# Replicape_B3.net
KiCad netlist of a schematic drawn in EAGLE
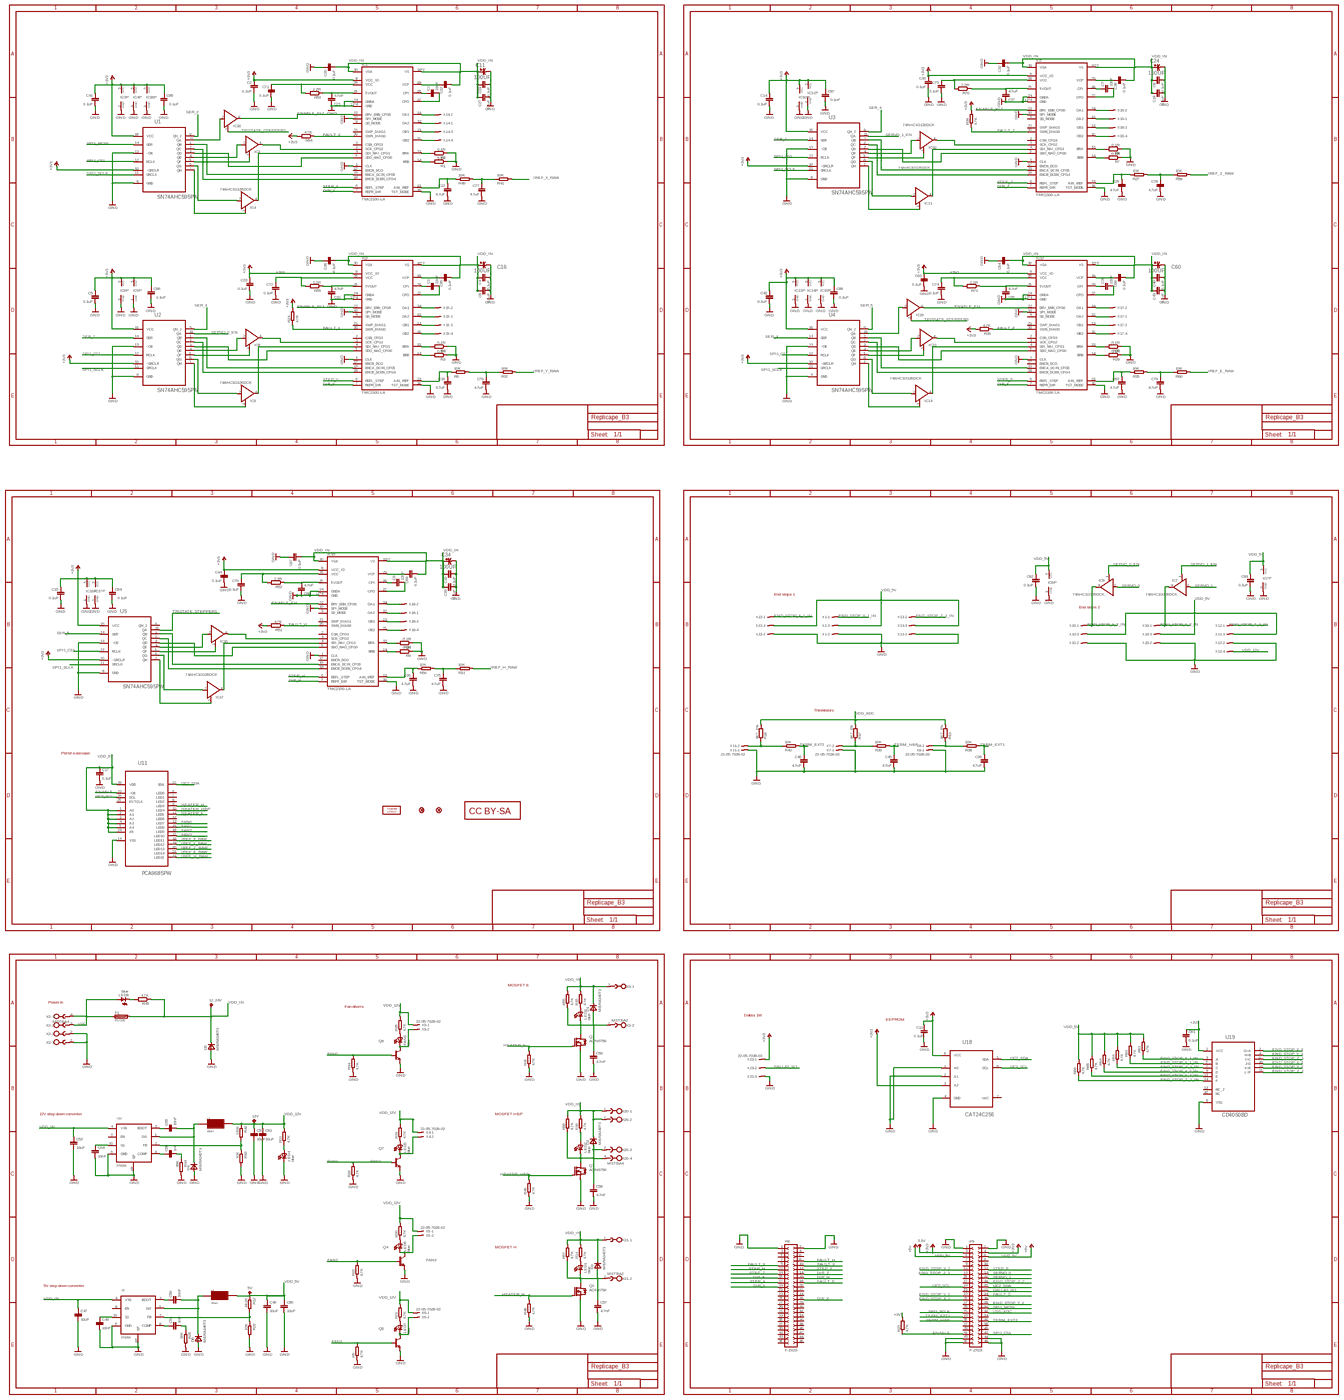
[diagram p0: schematic, sheet 1, overview]
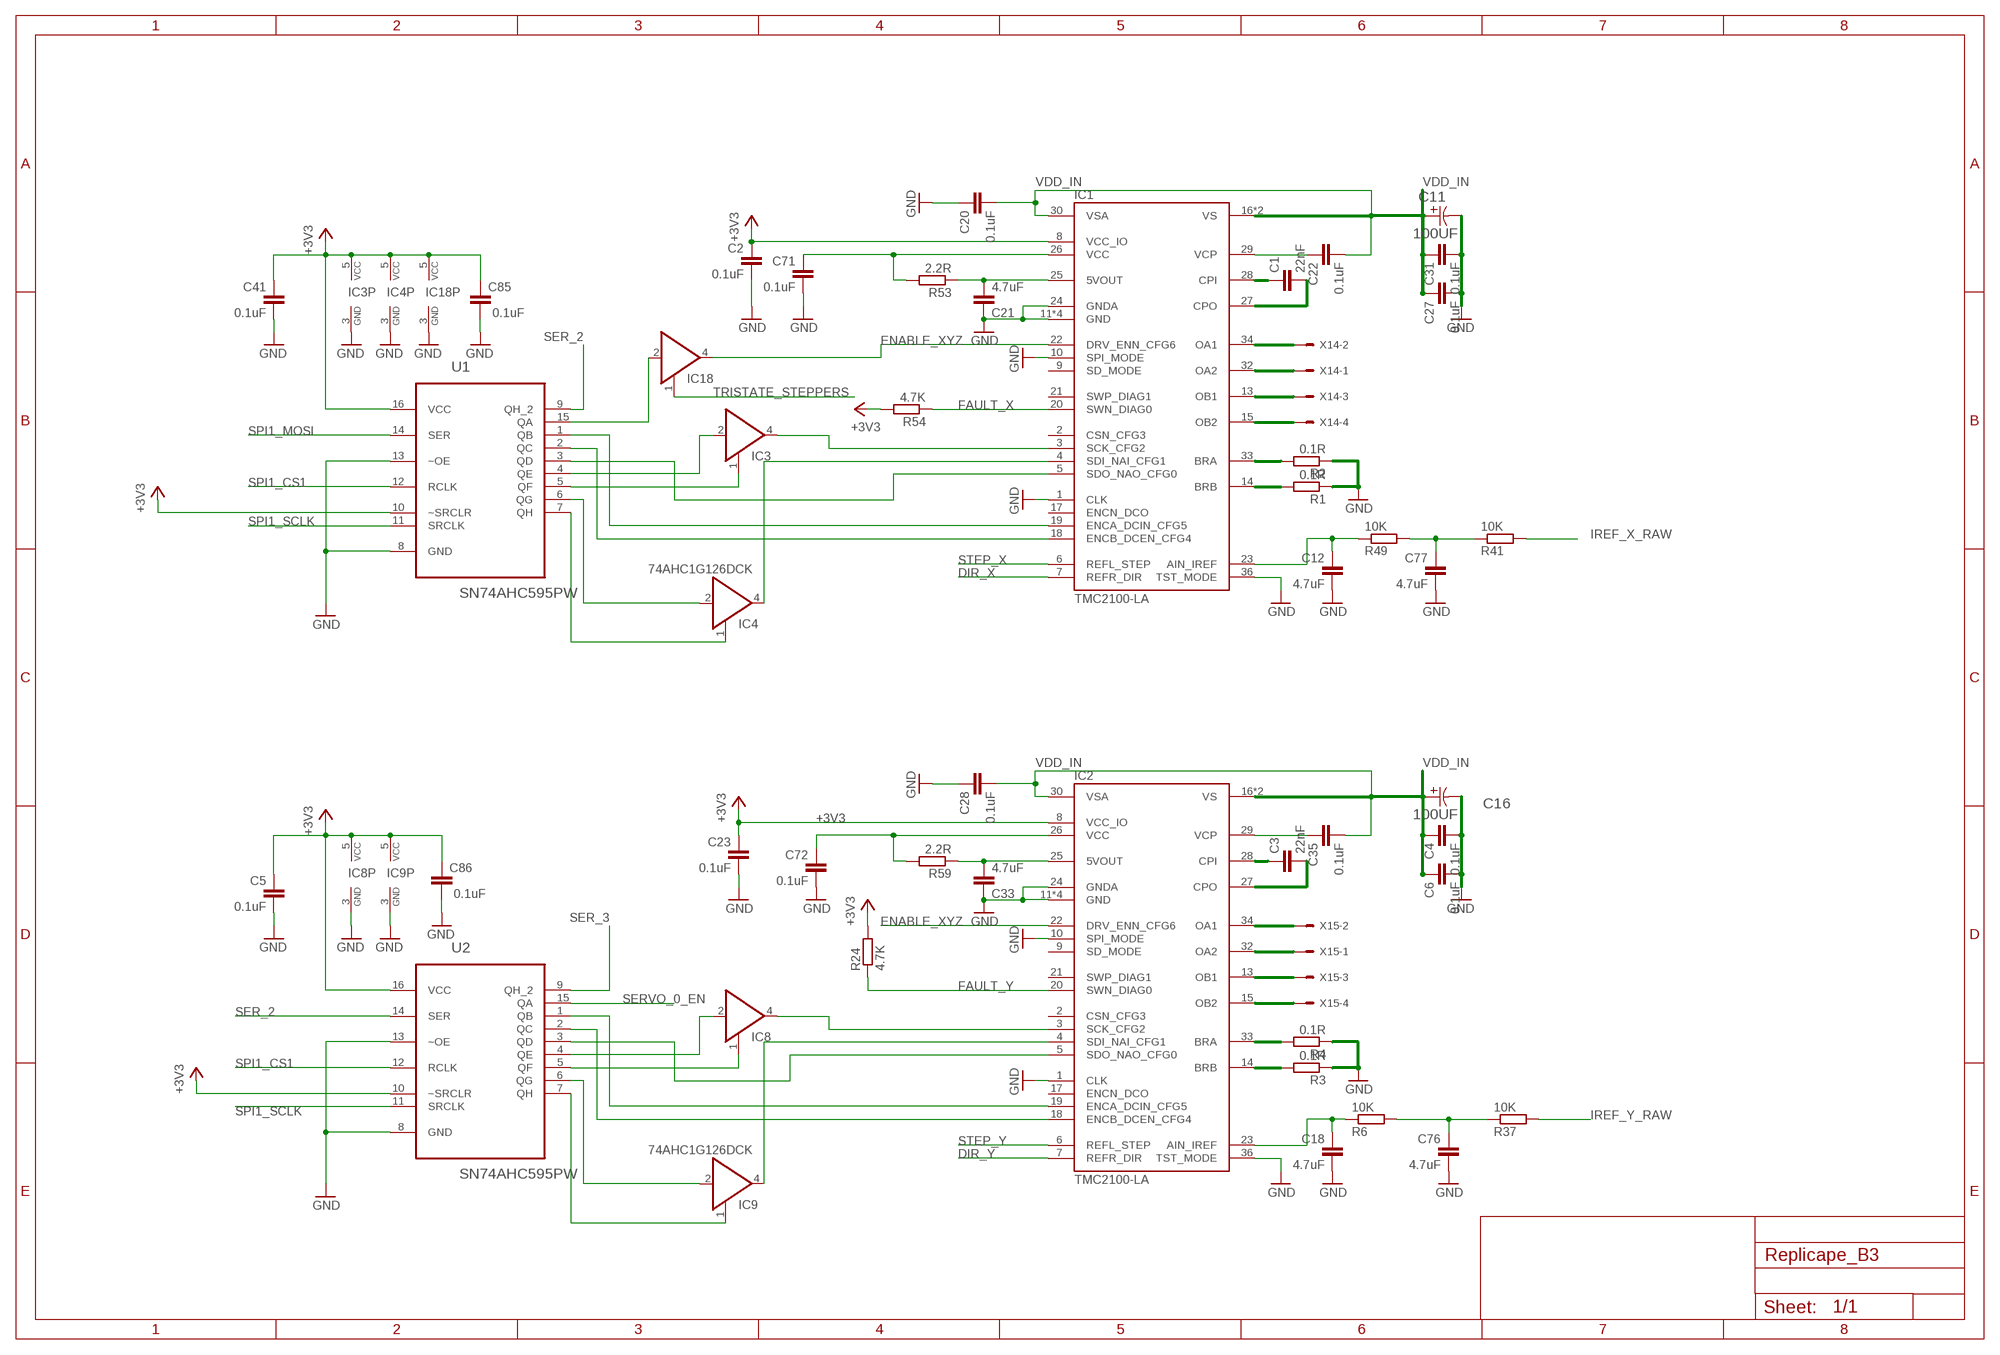
[diagram p1: schematic, sheet 1, part 1 of 4]
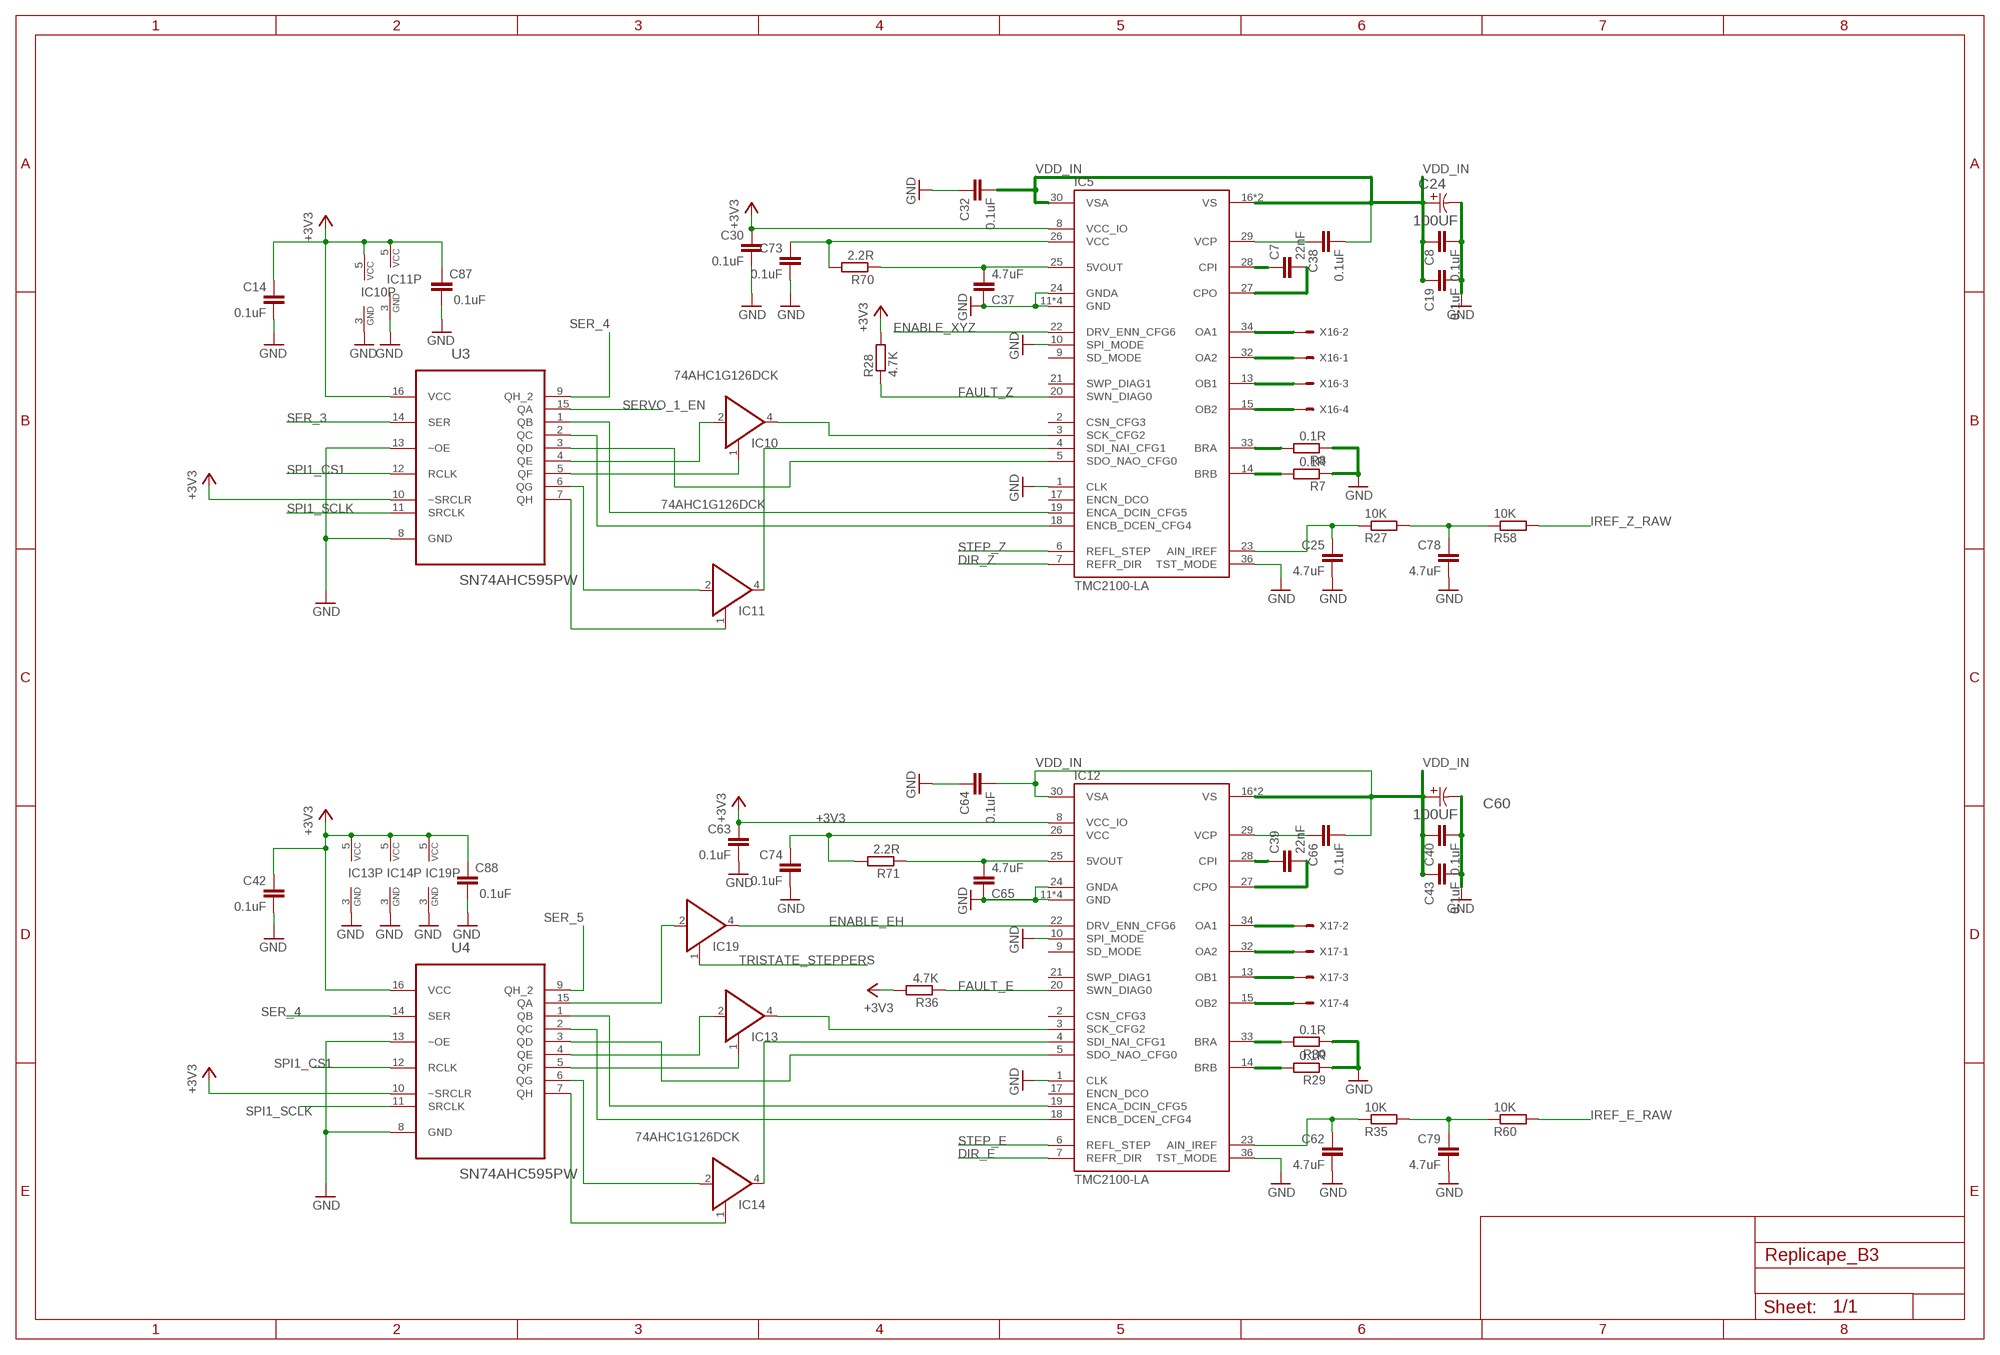
[diagram p2: schematic, sheet 1, part 2 of 4]
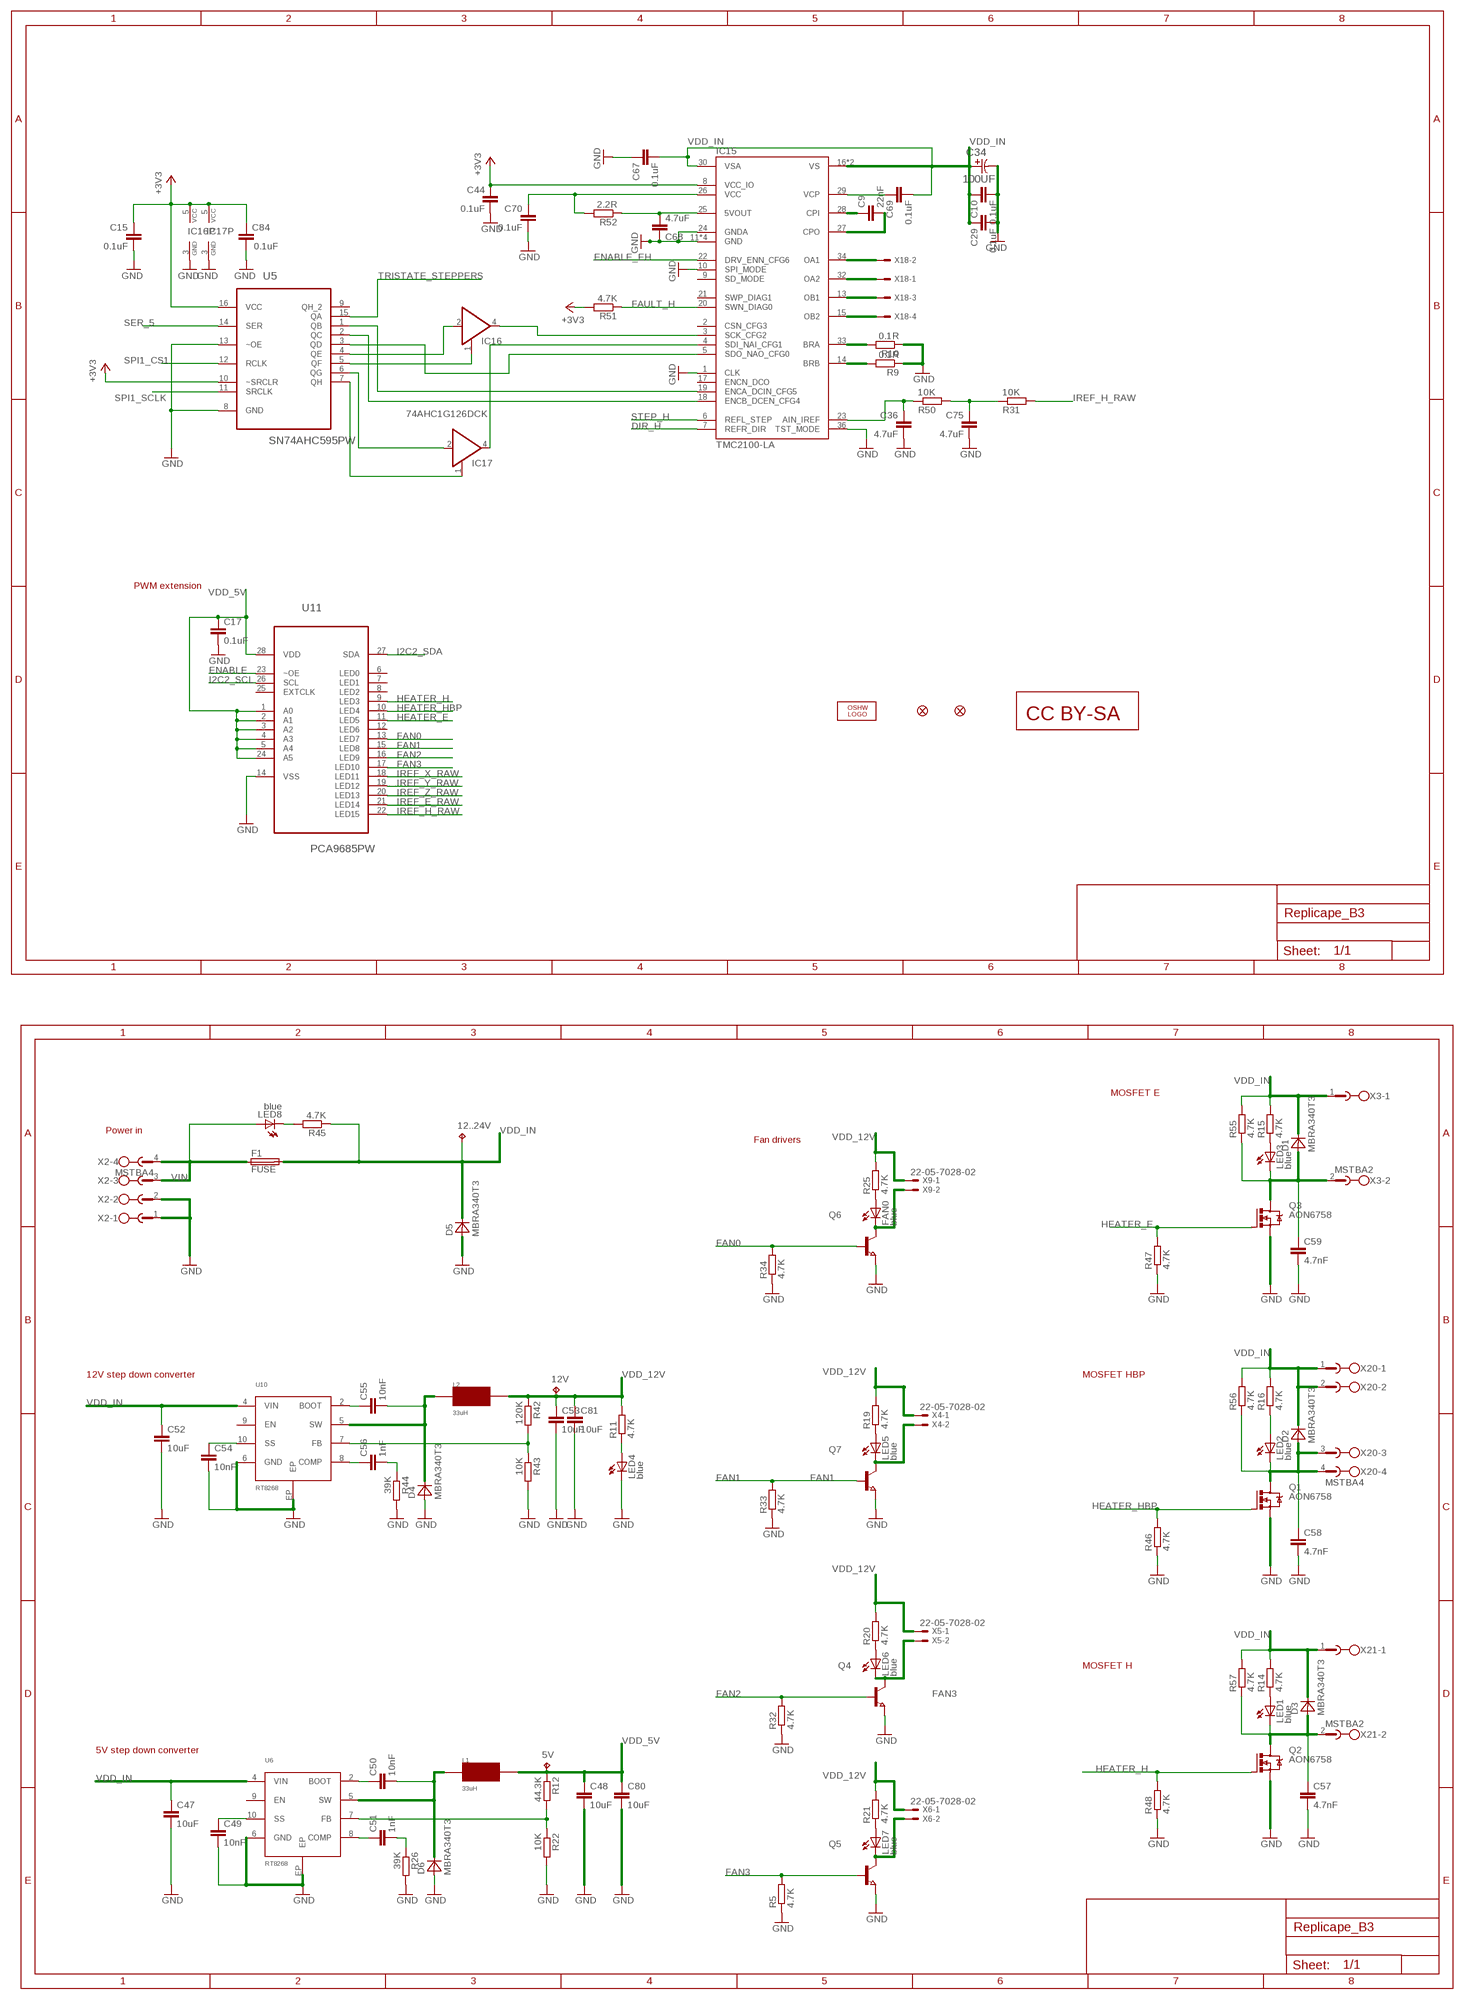
[diagram p3: schematic, sheet 1, part 3 of 4]
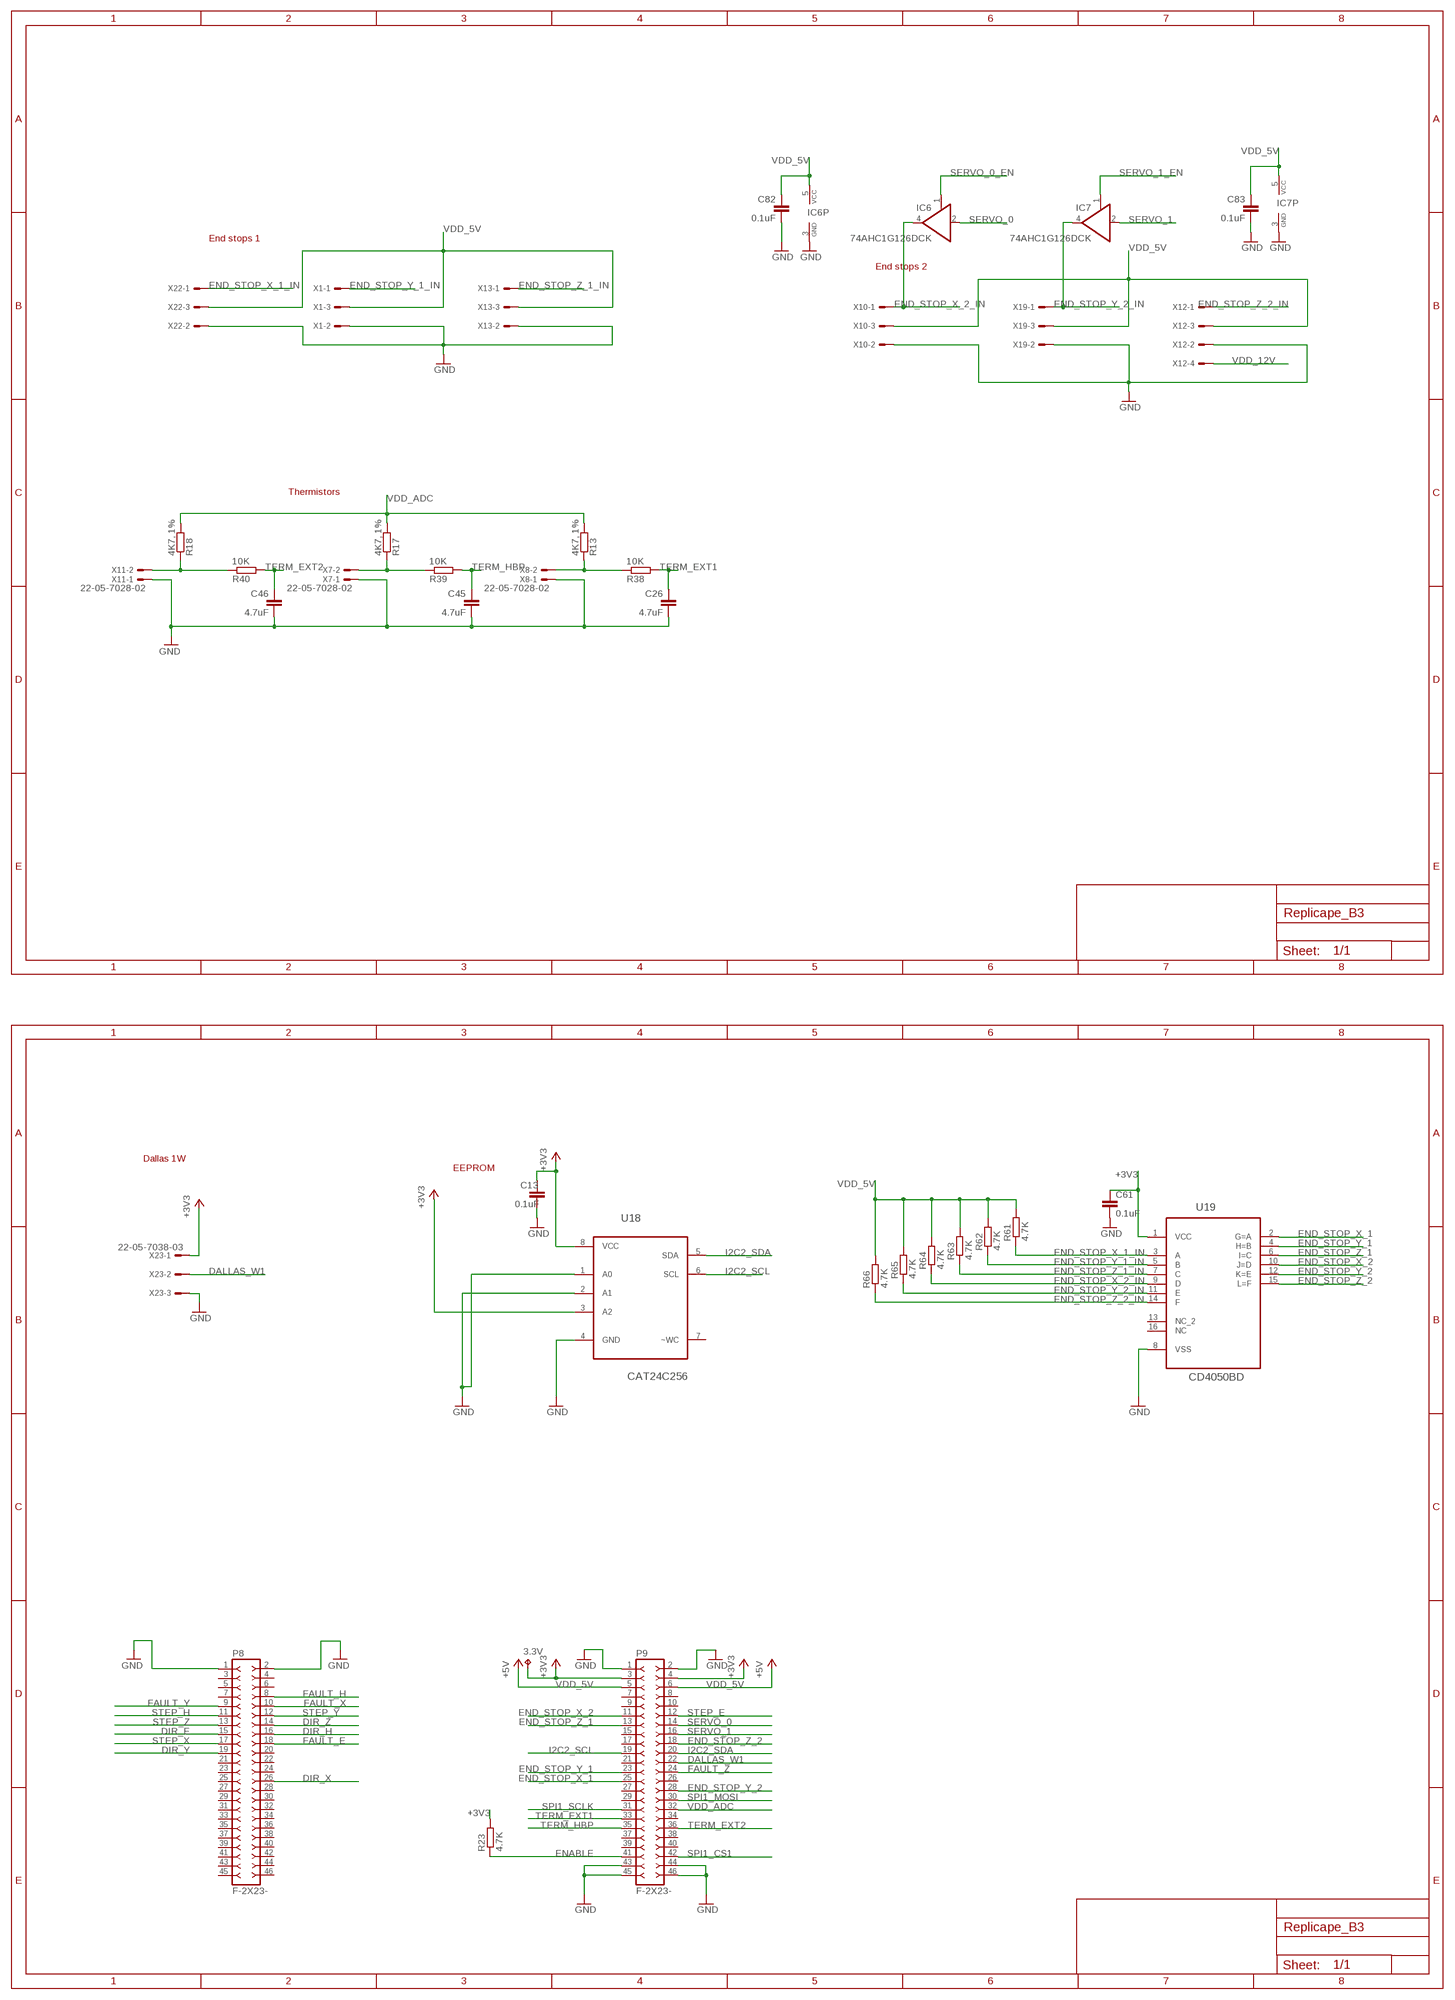
[diagram p4: schematic, sheet 1, part 4 of 4]

(export (version "E")
  (design (tool "Eeschema 10.0.6"))
  (components
    (comp (ref "3.3V")
      (value "TPB1,27")
      (footprint "eagle-import:B1,27")
      (libsource (lib "eagle-import") (part "TPB1,27"))
    )
    (comp (ref "5V")
      (value "TPB1,27")
      (footprint "eagle-import:B1,27")
      (libsource (lib "eagle-import") (part "TPB1,27"))
    )
    (comp (ref "12..24V")
      (value "TPB1,27")
      (footprint "eagle-import:B1,27")
      (libsource (lib "eagle-import") (part "TPB1,27"))
    )
    (comp (ref "12V")
      (value "TPB1,27")
      (footprint "eagle-import:B1,27")
      (libsource (lib "eagle-import") (part "TPB1,27"))
    )
    (comp (ref "C1")
      (value "22nF")
      (footprint "eagle-import:C0402")
      (libsource (lib "eagle-import") (part "C-EUC0402"))
    )
    (comp (ref "C2")
      (value "0.1uF")
      (footprint "eagle-import:C0402")
      (libsource (lib "eagle-import") (part "C-EUC0402"))
    )
    (comp (ref "C3")
      (value "22nF")
      (footprint "eagle-import:C0402")
      (libsource (lib "eagle-import") (part "C-EUC0402"))
    )
    (comp (ref "C4")
      (value "0.1uF")
      (footprint "eagle-import:C0402")
      (libsource (lib "eagle-import") (part "C-EUC0402"))
    )
    (comp (ref "C5")
      (value "0.1uF")
      (footprint "eagle-import:C0402")
      (libsource (lib "eagle-import") (part "C-EUC0402"))
    )
    (comp (ref "C6")
      (value "0.1uF")
      (footprint "eagle-import:C0402")
      (libsource (lib "eagle-import") (part "C-EUC0402"))
    )
    (comp (ref "C7")
      (value "22nF")
      (footprint "eagle-import:C0402")
      (libsource (lib "eagle-import") (part "C-EUC0402"))
    )
    (comp (ref "C8")
      (value "0.1uF")
      (footprint "eagle-import:C0402")
      (libsource (lib "eagle-import") (part "C-EUC0402"))
    )
    (comp (ref "C9")
      (value "22nF")
      (footprint "eagle-import:C0402")
      (libsource (lib "eagle-import") (part "C-EUC0402"))
    )
    (comp (ref "C10")
      (value "0.1uF")
      (footprint "eagle-import:C0402")
      (libsource (lib "eagle-import") (part "C-EUC0402"))
    )
    (comp (ref "C11")
      (value "100UF")
      (footprint "eagle-import:CAPAE660X800N")
      (fields (field (name "MPN") "EEE-FK1V101XP") (field (name "TOLERANCE") "±20 %"))
      (libsource (lib "eagle-import") (part "EEE--CASE-D8FK1V101XP"))
    )
    (comp (ref "C12")
      (value "4.7uF")
      (footprint "eagle-import:C0402")
      (libsource (lib "eagle-import") (part "C-EUC0402"))
    )
    (comp (ref "C13")
      (value "0.1uF")
      (footprint "eagle-import:C0402")
      (libsource (lib "eagle-import") (part "C-EUC0402"))
    )
    (comp (ref "C14")
      (value "0.1uF")
      (footprint "eagle-import:C0402")
      (libsource (lib "eagle-import") (part "C-EUC0402"))
    )
    (comp (ref "C15")
      (value "0.1uF")
      (footprint "eagle-import:C0402")
      (libsource (lib "eagle-import") (part "C-EUC0402"))
    )
    (comp (ref "C16")
      (value "100UF")
      (footprint "eagle-import:CAPAE660X800N")
      (fields (field (name "MPN") "EEE-FK1V101XP") (field (name "TOLERANCE") "±20 %"))
      (libsource (lib "eagle-import") (part "EEE--CASE-D8FK1V101XP"))
    )
    (comp (ref "C17")
      (value "0.1uF")
      (footprint "eagle-import:C0402")
      (libsource (lib "eagle-import") (part "C-EUC0402"))
    )
    (comp (ref "C18")
      (value "4.7uF")
      (footprint "eagle-import:C0402")
      (libsource (lib "eagle-import") (part "C-EUC0402"))
    )
    (comp (ref "C19")
      (value "0.1uF")
      (footprint "eagle-import:C0402")
      (libsource (lib "eagle-import") (part "C-EUC0402"))
    )
    (comp (ref "C20")
      (value "0.1uF")
      (footprint "eagle-import:C0402")
      (libsource (lib "eagle-import") (part "C-EUC0402"))
    )
    (comp (ref "C21")
      (value "4.7uF")
      (footprint "eagle-import:C0402")
      (libsource (lib "eagle-import") (part "C-EUC0402"))
    )
    (comp (ref "C22")
      (value "0.1uF")
      (footprint "eagle-import:C0402")
      (libsource (lib "eagle-import") (part "C-EUC0402"))
    )
    (comp (ref "C23")
      (value "0.1uF")
      (footprint "eagle-import:C0402")
      (libsource (lib "eagle-import") (part "C-EUC0402"))
    )
    (comp (ref "C24")
      (value "100UF")
      (footprint "eagle-import:CAPAE660X800N")
      (fields (field (name "MPN") "EEE-FK1V101XP") (field (name "TOLERANCE") "±20 %"))
      (libsource (lib "eagle-import") (part "EEE--CASE-D8FK1V101XP"))
    )
    (comp (ref "C25")
      (value "4.7uF")
      (footprint "eagle-import:C0402")
      (libsource (lib "eagle-import") (part "C-EUC0402"))
    )
    (comp (ref "C26")
      (value "4.7uF")
      (footprint "eagle-import:C0402")
      (libsource (lib "eagle-import") (part "C-EUC0402"))
    )
    (comp (ref "C27")
      (value "0.1uF")
      (footprint "eagle-import:C0402")
      (libsource (lib "eagle-import") (part "C-EUC0402"))
    )
    (comp (ref "C28")
      (value "0.1uF")
      (footprint "eagle-import:C0402")
      (libsource (lib "eagle-import") (part "C-EUC0402"))
    )
    (comp (ref "C29")
      (value "0.1uF")
      (footprint "eagle-import:C0402")
      (libsource (lib "eagle-import") (part "C-EUC0402"))
    )
    (comp (ref "C30")
      (value "0.1uF")
      (footprint "eagle-import:C0402")
      (libsource (lib "eagle-import") (part "C-EUC0402"))
    )
    (comp (ref "C31")
      (value "0.1uF")
      (footprint "eagle-import:C0402")
      (libsource (lib "eagle-import") (part "C-EUC0402"))
    )
    (comp (ref "C32")
      (value "0.1uF")
      (footprint "eagle-import:C0402")
      (libsource (lib "eagle-import") (part "C-EUC0402"))
    )
    (comp (ref "C33")
      (value "4.7uF")
      (footprint "eagle-import:C0402")
      (libsource (lib "eagle-import") (part "C-EUC0402"))
    )
    (comp (ref "C34")
      (value "100UF")
      (footprint "eagle-import:CAPAE660X800N")
      (fields (field (name "MPN") "EEE-FK1V101XP") (field (name "TOLERANCE") "±20 %"))
      (libsource (lib "eagle-import") (part "EEE--CASE-D8FK1V101XP"))
    )
    (comp (ref "C35")
      (value "0.1uF")
      (footprint "eagle-import:C0402")
      (libsource (lib "eagle-import") (part "C-EUC0402"))
    )
    (comp (ref "C36")
      (value "4.7uF")
      (footprint "eagle-import:C0402")
      (libsource (lib "eagle-import") (part "C-EUC0402"))
    )
    (comp (ref "C37")
      (value "4.7uF")
      (footprint "eagle-import:C0402")
      (libsource (lib "eagle-import") (part "C-EUC0402"))
    )
    (comp (ref "C38")
      (value "0.1uF")
      (footprint "eagle-import:C0402")
      (libsource (lib "eagle-import") (part "C-EUC0402"))
    )
    (comp (ref "C39")
      (value "22nF")
      (footprint "eagle-import:C0402")
      (libsource (lib "eagle-import") (part "C-EUC0402"))
    )
    (comp (ref "C40")
      (value "0.1uF")
      (footprint "eagle-import:C0402")
      (libsource (lib "eagle-import") (part "C-EUC0402"))
    )
    (comp (ref "C41")
      (value "0.1uF")
      (footprint "eagle-import:C0402")
      (libsource (lib "eagle-import") (part "C-EUC0402"))
    )
    (comp (ref "C42")
      (value "0.1uF")
      (footprint "eagle-import:C0402")
      (libsource (lib "eagle-import") (part "C-EUC0402"))
    )
    (comp (ref "C43")
      (value "0.1uF")
      (footprint "eagle-import:C0402")
      (libsource (lib "eagle-import") (part "C-EUC0402"))
    )
    (comp (ref "C44")
      (value "0.1uF")
      (footprint "eagle-import:C0402")
      (libsource (lib "eagle-import") (part "C-EUC0402"))
    )
    (comp (ref "C45")
      (value "4.7uF")
      (footprint "eagle-import:C0402")
      (libsource (lib "eagle-import") (part "C-EUC0402"))
    )
    (comp (ref "C46")
      (value "4.7uF")
      (footprint "eagle-import:C0402")
      (libsource (lib "eagle-import") (part "C-EUC0402"))
    )
    (comp (ref "C47")
      (value "10uF")
      (footprint "eagle-import:C1206")
      (libsource (lib "eagle-import") (part "C-EUC1206"))
    )
    (comp (ref "C48")
      (value "10uF")
      (footprint "eagle-import:C1206")
      (libsource (lib "eagle-import") (part "C-EUC1206"))
    )
    (comp (ref "C49")
      (value "10nF")
      (footprint "eagle-import:C0402")
      (libsource (lib "eagle-import") (part "C-EUC0402"))
    )
    (comp (ref "C50")
      (value "10nF")
      (footprint "eagle-import:C0402")
      (libsource (lib "eagle-import") (part "C-EUC0402"))
    )
    (comp (ref "C51")
      (value "1nF")
      (footprint "eagle-import:C0402")
      (libsource (lib "eagle-import") (part "C-EUC0402"))
    )
    (comp (ref "C52")
      (value "10uF")
      (footprint "eagle-import:C1206")
      (libsource (lib "eagle-import") (part "C-EUC1206"))
    )
    (comp (ref "C53")
      (value "10uF")
      (footprint "eagle-import:C1206")
      (libsource (lib "eagle-import") (part "C-EUC1206"))
    )
    (comp (ref "C54")
      (value "10nF")
      (footprint "eagle-import:C0402")
      (libsource (lib "eagle-import") (part "C-EUC0402"))
    )
    (comp (ref "C55")
      (value "10nF")
      (footprint "eagle-import:C0402")
      (libsource (lib "eagle-import") (part "C-EUC0402"))
    )
    (comp (ref "C56")
      (value "1nF")
      (footprint "eagle-import:C0402")
      (libsource (lib "eagle-import") (part "C-EUC0402"))
    )
    (comp (ref "C57")
      (value "4.7nF")
      (footprint "eagle-import:C0402")
      (libsource (lib "eagle-import") (part "C-EUC0402"))
    )
    (comp (ref "C58")
      (value "4.7nF")
      (footprint "eagle-import:C0402")
      (libsource (lib "eagle-import") (part "C-EUC0402"))
    )
    (comp (ref "C59")
      (value "4.7nF")
      (footprint "eagle-import:C0402")
      (libsource (lib "eagle-import") (part "C-EUC0402"))
    )
    (comp (ref "C60")
      (value "100UF")
      (footprint "eagle-import:CAPAE660X800N")
      (fields (field (name "MPN") "EEE-FK1V101XP") (field (name "TOLERANCE") "±20 %"))
      (libsource (lib "eagle-import") (part "EEE--CASE-D8FK1V101XP"))
    )
    (comp (ref "C61")
      (value "0.1uF")
      (footprint "eagle-import:C0402")
      (libsource (lib "eagle-import") (part "C-EUC0402"))
    )
    (comp (ref "C62")
      (value "4.7uF")
      (footprint "eagle-import:C0402")
      (libsource (lib "eagle-import") (part "C-EUC0402"))
    )
    (comp (ref "C63")
      (value "0.1uF")
      (footprint "eagle-import:C0402")
      (libsource (lib "eagle-import") (part "C-EUC0402"))
    )
    (comp (ref "C64")
      (value "0.1uF")
      (footprint "eagle-import:C0402")
      (libsource (lib "eagle-import") (part "C-EUC0402"))
    )
    (comp (ref "C65")
      (value "4.7uF")
      (footprint "eagle-import:C0402")
      (libsource (lib "eagle-import") (part "C-EUC0402"))
    )
    (comp (ref "C66")
      (value "0.1uF")
      (footprint "eagle-import:C0402")
      (libsource (lib "eagle-import") (part "C-EUC0402"))
    )
    (comp (ref "C67")
      (value "0.1uF")
      (footprint "eagle-import:C0402")
      (libsource (lib "eagle-import") (part "C-EUC0402"))
    )
    (comp (ref "C68")
      (value "4.7uF")
      (footprint "eagle-import:C0402")
      (libsource (lib "eagle-import") (part "C-EUC0402"))
    )
    (comp (ref "C69")
      (value "0.1uF")
      (footprint "eagle-import:C0402")
      (libsource (lib "eagle-import") (part "C-EUC0402"))
    )
    (comp (ref "C70")
      (value "0.1uF")
      (footprint "eagle-import:C0402")
      (libsource (lib "eagle-import") (part "C-EUC0402"))
    )
    (comp (ref "C71")
      (value "0.1uF")
      (footprint "eagle-import:C0402")
      (libsource (lib "eagle-import") (part "C-EUC0402"))
    )
    (comp (ref "C72")
      (value "0.1uF")
      (footprint "eagle-import:C0402")
      (libsource (lib "eagle-import") (part "C-EUC0402"))
    )
    (comp (ref "C73")
      (value "0.1uF")
      (footprint "eagle-import:C0402")
      (libsource (lib "eagle-import") (part "C-EUC0402"))
    )
    (comp (ref "C74")
      (value "0.1uF")
      (footprint "eagle-import:C0402")
      (libsource (lib "eagle-import") (part "C-EUC0402"))
    )
    (comp (ref "C75")
      (value "4.7uF")
      (footprint "eagle-import:C0402")
      (libsource (lib "eagle-import") (part "C-EUC0402"))
    )
    (comp (ref "C76")
      (value "4.7uF")
      (footprint "eagle-import:C0402")
      (libsource (lib "eagle-import") (part "C-EUC0402"))
    )
    (comp (ref "C77")
      (value "4.7uF")
      (footprint "eagle-import:C0402")
      (libsource (lib "eagle-import") (part "C-EUC0402"))
    )
    (comp (ref "C78")
      (value "4.7uF")
      (footprint "eagle-import:C0402")
      (libsource (lib "eagle-import") (part "C-EUC0402"))
    )
    (comp (ref "C79")
      (value "4.7uF")
      (footprint "eagle-import:C0402")
      (libsource (lib "eagle-import") (part "C-EUC0402"))
    )
    (comp (ref "C80")
      (value "10uF")
      (footprint "eagle-import:C1206")
      (libsource (lib "eagle-import") (part "C-EUC1206"))
    )
    (comp (ref "C81")
      (value "10uF")
      (footprint "eagle-import:C1206")
      (libsource (lib "eagle-import") (part "C-EUC1206"))
    )
    (comp (ref "C82")
      (value "0.1uF")
      (footprint "eagle-import:C0402")
      (libsource (lib "eagle-import") (part "C-EUC0402"))
    )
    (comp (ref "C83")
      (value "0.1uF")
      (footprint "eagle-import:C0402")
      (libsource (lib "eagle-import") (part "C-EUC0402"))
    )
    (comp (ref "C84")
      (value "0.1uF")
      (footprint "eagle-import:C0402")
      (libsource (lib "eagle-import") (part "C-EUC0402"))
    )
    (comp (ref "C85")
      (value "0.1uF")
      (footprint "eagle-import:C0402")
      (libsource (lib "eagle-import") (part "C-EUC0402"))
    )
    (comp (ref "C86")
      (value "0.1uF")
      (footprint "eagle-import:C0402")
      (libsource (lib "eagle-import") (part "C-EUC0402"))
    )
    (comp (ref "C87")
      (value "0.1uF")
      (footprint "eagle-import:C0402")
      (libsource (lib "eagle-import") (part "C-EUC0402"))
    )
    (comp (ref "C88")
      (value "0.1uF")
      (footprint "eagle-import:C0402")
      (libsource (lib "eagle-import") (part "C-EUC0402"))
    )
    (comp (ref "D1")
      (value "MBRA340T3")
      (footprint "eagle-import:SMA")
      (libsource (lib "eagle-import") (part "MBRA340T3"))
    )
    (comp (ref "D2")
      (value "MBRA340T3")
      (footprint "eagle-import:SMA")
      (libsource (lib "eagle-import") (part "MBRA340T3"))
    )
    (comp (ref "D3")
      (value "MBRA340T3")
      (footprint "eagle-import:SMA")
      (libsource (lib "eagle-import") (part "MBRA340T3"))
    )
    (comp (ref "D4")
      (value "MBRA340T3")
      (footprint "eagle-import:SMA")
      (libsource (lib "eagle-import") (part "MBRA340T3"))
    )
    (comp (ref "D5")
      (value "MBRA340T3")
      (footprint "eagle-import:SMA")
      (libsource (lib "eagle-import") (part "MBRA340T3"))
    )
    (comp (ref "D6")
      (value "MBRA340T3")
      (footprint "eagle-import:SMA")
      (libsource (lib "eagle-import") (part "MBRA340T3"))
    )
    (comp (ref "F1")
      (value "FUSE")
      (footprint "eagle-import:3557")
      (libsource (lib "eagle-import") (part "FUSE"))
    )
    (comp (ref "FAN0")
      (value "blue")
      (footprint "eagle-import:CHIP-LED0603")
      (libsource (lib "eagle-import") (part "LEDCHIP-LED0603"))
    )
    (comp (ref "IC1")
      (value "TMC2100-LA")
      (footprint "eagle-import:QFN36-PAD")
      (libsource (lib "eagle-import") (part "TMC2100-LA"))
    )
    (comp (ref "IC2")
      (value "TMC2100-LA")
      (footprint "eagle-import:QFN36-PAD")
      (libsource (lib "eagle-import") (part "TMC2100-LA"))
    )
    (comp (ref "IC3")
      (value "74AHC1G126DCK")
      (footprint "eagle-import:SC70-5")
      (libsource (lib "eagle-import") (part "741G126DCKAHC"))
    )
    (comp (ref "IC4")
      (value "74AHC1G126DCK")
      (footprint "eagle-import:SC70-5")
      (libsource (lib "eagle-import") (part "741G126DCKAHC"))
    )
    (comp (ref "IC5")
      (value "TMC2100-LA")
      (footprint "eagle-import:QFN36-PAD")
      (libsource (lib "eagle-import") (part "TMC2100-LA"))
    )
    (comp (ref "IC6")
      (value "74AHC1G126DCK")
      (footprint "eagle-import:SC70-5")
      (libsource (lib "eagle-import") (part "741G126DCKAHC"))
    )
    (comp (ref "IC7")
      (value "74AHC1G126DCK")
      (footprint "eagle-import:SC70-5")
      (libsource (lib "eagle-import") (part "741G126DCKAHC"))
    )
    (comp (ref "IC8")
      (value "74AHC1G126DCK")
      (footprint "eagle-import:SC70-5")
      (libsource (lib "eagle-import") (part "741G126DCKAHC"))
    )
    (comp (ref "IC9")
      (value "74AHC1G126DCK")
      (footprint "eagle-import:SC70-5")
      (libsource (lib "eagle-import") (part "741G126DCKAHC"))
    )
    (comp (ref "IC10")
      (value "74AHC1G126DCK")
      (footprint "eagle-import:SC70-5")
      (libsource (lib "eagle-import") (part "741G126DCKAHC"))
    )
    (comp (ref "IC11")
      (value "74AHC1G126DCK")
      (footprint "eagle-import:SC70-5")
      (libsource (lib "eagle-import") (part "741G126DCKAHC"))
    )
    (comp (ref "IC12")
      (value "TMC2100-LA")
      (footprint "eagle-import:QFN36-PAD")
      (libsource (lib "eagle-import") (part "TMC2100-LA"))
    )
    (comp (ref "IC13")
      (value "74AHC1G126DCK")
      (footprint "eagle-import:SC70-5")
      (libsource (lib "eagle-import") (part "741G126DCKAHC"))
    )
    (comp (ref "IC14")
      (value "74AHC1G126DCK")
      (footprint "eagle-import:SC70-5")
      (libsource (lib "eagle-import") (part "741G126DCKAHC"))
    )
    (comp (ref "IC15")
      (value "TMC2100-LA")
      (footprint "eagle-import:QFN36-PAD")
      (libsource (lib "eagle-import") (part "TMC2100-LA"))
    )
    (comp (ref "IC16")
      (value "74AHC1G126DCK")
      (footprint "eagle-import:SC70-5")
      (libsource (lib "eagle-import") (part "741G126DCKAHC"))
    )
    (comp (ref "IC17")
      (value "74AHC1G126DCK")
      (footprint "eagle-import:SC70-5")
      (libsource (lib "eagle-import") (part "741G126DCKAHC"))
    )
    (comp (ref "IC18")
      (value "74AHC1G126DCK")
      (footprint "eagle-import:SC70-5")
      (libsource (lib "eagle-import") (part "741G126DCKAHC"))
    )
    (comp (ref "IC19")
      (value "74AHC1G126DCK")
      (footprint "eagle-import:SC70-5")
      (libsource (lib "eagle-import") (part "741G126DCKAHC"))
    )
    (comp (ref "JP1")
      (value "FIDUCIAL1X2.5")
      (footprint "eagle-import:FIDUCIAL-1X2.5")
      (libsource (lib "eagle-import") (part "FIDUCIAL1X2.5"))
    )
    (comp (ref "JP2")
      (value "FIDUCIAL1X2.5")
      (footprint "eagle-import:FIDUCIAL-1X2.5")
      (libsource (lib "eagle-import") (part "FIDUCIAL1X2.5"))
    )
    (comp (ref "L1")
      (value "33uH")
      (footprint "eagle-import:NR8040T330")
      (libsource (lib "eagle-import") (part "RT8040T330"))
    )
    (comp (ref "L2")
      (value "33uH")
      (footprint "eagle-import:NR8040T330")
      (libsource (lib "eagle-import") (part "RT8040T330"))
    )
    (comp (ref "LED1")
      (value "blue")
      (footprint "eagle-import:CHIP-LED0603")
      (libsource (lib "eagle-import") (part "LEDCHIP-LED0603"))
    )
    (comp (ref "LED2")
      (value "blue")
      (footprint "eagle-import:CHIP-LED0603")
      (libsource (lib "eagle-import") (part "LEDCHIP-LED0603"))
    )
    (comp (ref "LED3")
      (value "blue")
      (footprint "eagle-import:CHIP-LED0603")
      (libsource (lib "eagle-import") (part "LEDCHIP-LED0603"))
    )
    (comp (ref "LED4")
      (value "blue")
      (footprint "eagle-import:CHIP-LED0603")
      (libsource (lib "eagle-import") (part "LEDCHIP-LED0603"))
    )
    (comp (ref "LED5")
      (value "blue")
      (footprint "eagle-import:CHIP-LED0603")
      (libsource (lib "eagle-import") (part "LEDCHIP-LED0603"))
    )
    (comp (ref "LED6")
      (value "blue")
      (footprint "eagle-import:CHIP-LED0603")
      (libsource (lib "eagle-import") (part "LEDCHIP-LED0603"))
    )
    (comp (ref "LED7")
      (value "blue")
      (footprint "eagle-import:CHIP-LED0603")
      (libsource (lib "eagle-import") (part "LEDCHIP-LED0603"))
    )
    (comp (ref "LED8")
      (value "blue")
      (footprint "eagle-import:CHIP-LED0603")
      (libsource (lib "eagle-import") (part "LEDCHIP-LED0603"))
    )
    (comp (ref "LOGO1")
      (value "OSHW_LOGO_FILLX0200-NT")
      (footprint "eagle-import:OSHW_FILLX200_NOTEXT")
      (libsource (lib "eagle-import") (part "OSHW_LOGO_FILLX0200-NT"))
    )
    (comp (ref "P8")
      (value "F-2X23-")
      (footprint "eagle-import:DIL-100-2X23")
      (libsource (lib "eagle-import") (part "F-2X23-"))
    )
    (comp (ref "P9")
      (value "F-2X23-")
      (footprint "eagle-import:DIL-100-2X23")
      (libsource (lib "eagle-import") (part "F-2X23-"))
    )
    (comp (ref "Q1")
      (value "AON6758")
      (footprint "eagle-import:8-DFN-EP-(5X6)")
      (libsource (lib "eagle-import") (part "AON6758"))
    )
    (comp (ref "Q2")
      (value "AON6758")
      (footprint "eagle-import:8-DFN-EP-(5X6)")
      (libsource (lib "eagle-import") (part "AON6758"))
    )
    (comp (ref "Q3")
      (value "AON6758")
      (footprint "eagle-import:8-DFN-EP-(5X6)")
      (libsource (lib "eagle-import") (part "AON6758"))
    )
    (comp (ref "Q4")
      (value "NPN-TRANSISTOR_SOT23")
      (footprint "eagle-import:SOT23")
      (libsource (lib "eagle-import") (part "NPN-TRANSISTOR_SOT23"))
    )
    (comp (ref "Q5")
      (value "NPN-TRANSISTOR_SOT23")
      (footprint "eagle-import:SOT23")
      (libsource (lib "eagle-import") (part "NPN-TRANSISTOR_SOT23"))
    )
    (comp (ref "Q6")
      (value "NPN-TRANSISTOR_SOT23")
      (footprint "eagle-import:SOT23")
      (libsource (lib "eagle-import") (part "NPN-TRANSISTOR_SOT23"))
    )
    (comp (ref "Q7")
      (value "NPN-TRANSISTOR_SOT23")
      (footprint "eagle-import:SOT23")
      (libsource (lib "eagle-import") (part "NPN-TRANSISTOR_SOT23"))
    )
    (comp (ref "R1")
      (value "0.1R")
      (footprint "eagle-import:R0805")
      (libsource (lib "eagle-import") (part "R-EU_R0805"))
    )
    (comp (ref "R2")
      (value "0.1R")
      (footprint "eagle-import:R0805")
      (libsource (lib "eagle-import") (part "R-EU_R0805"))
    )
    (comp (ref "R3")
      (value "0.1R")
      (footprint "eagle-import:R0805")
      (libsource (lib "eagle-import") (part "R-EU_R0805"))
    )
    (comp (ref "R4")
      (value "0.1R")
      (footprint "eagle-import:R0805")
      (libsource (lib "eagle-import") (part "R-EU_R0805"))
    )
    (comp (ref "R5")
      (value "4.7K")
      (footprint "eagle-import:R0402")
      (libsource (lib "eagle-import") (part "R-EU_R0402"))
    )
    (comp (ref "R6")
      (value "10K")
      (footprint "eagle-import:R0402")
      (libsource (lib "eagle-import") (part "R-EU_R0402"))
    )
    (comp (ref "R7")
      (value "0.1R")
      (footprint "eagle-import:R0805")
      (libsource (lib "eagle-import") (part "R-EU_R0805"))
    )
    (comp (ref "R8")
      (value "0.1R")
      (footprint "eagle-import:R0805")
      (libsource (lib "eagle-import") (part "R-EU_R0805"))
    )
    (comp (ref "R9")
      (value "0.1R")
      (footprint "eagle-import:R0805")
      (libsource (lib "eagle-import") (part "R-EU_R0805"))
    )
    (comp (ref "R10")
      (value "0.1R")
      (footprint "eagle-import:R0805")
      (libsource (lib "eagle-import") (part "R-EU_R0805"))
    )
    (comp (ref "R11")
      (value "4.7K")
      (footprint "eagle-import:R0402")
      (libsource (lib "eagle-import") (part "R-EU_R0402"))
    )
    (comp (ref "R12")
      (value "44.3K")
      (footprint "eagle-import:R0402")
      (libsource (lib "eagle-import") (part "R-EU_R0402"))
    )
    (comp (ref "R13")
      (value "4K7, 1%")
      (footprint "eagle-import:R0402")
      (libsource (lib "eagle-import") (part "R-EU_R0402"))
    )
    (comp (ref "R14")
      (value "4.7K")
      (footprint "eagle-import:R0402")
      (libsource (lib "eagle-import") (part "R-EU_R0402"))
    )
    (comp (ref "R15")
      (value "4.7K")
      (footprint "eagle-import:R0402")
      (libsource (lib "eagle-import") (part "R-EU_R0402"))
    )
    (comp (ref "R16")
      (value "4.7K")
      (footprint "eagle-import:R0402")
      (libsource (lib "eagle-import") (part "R-EU_R0402"))
    )
    (comp (ref "R17")
      (value "4K7, 1%")
      (footprint "eagle-import:R0402")
      (libsource (lib "eagle-import") (part "R-EU_R0402"))
    )
    (comp (ref "R18")
      (value "4K7, 1%")
      (footprint "eagle-import:R0402")
      (libsource (lib "eagle-import") (part "R-EU_R0402"))
    )
    (comp (ref "R19")
      (value "4.7K")
      (footprint "eagle-import:R0402")
      (libsource (lib "eagle-import") (part "R-EU_R0402"))
    )
    (comp (ref "R20")
      (value "4.7K")
      (footprint "eagle-import:R0402")
      (libsource (lib "eagle-import") (part "R-EU_R0402"))
    )
    (comp (ref "R21")
      (value "4.7K")
      (footprint "eagle-import:R0402")
      (libsource (lib "eagle-import") (part "R-EU_R0402"))
    )
    (comp (ref "R22")
      (value "10K")
      (footprint "eagle-import:R0402")
      (libsource (lib "eagle-import") (part "R-EU_R0402"))
    )
    (comp (ref "R23")
      (value "4.7K")
      (footprint "eagle-import:R0402")
      (libsource (lib "eagle-import") (part "R-EU_R0402"))
    )
    (comp (ref "R24")
      (value "4.7K")
      (footprint "eagle-import:R0402")
      (libsource (lib "eagle-import") (part "R-EU_R0402"))
    )
    (comp (ref "R25")
      (value "4.7K")
      (footprint "eagle-import:R0402")
      (libsource (lib "eagle-import") (part "R-EU_R0402"))
    )
    (comp (ref "R26")
      (value "39K")
      (footprint "eagle-import:R0402")
      (libsource (lib "eagle-import") (part "R-EU_R0402"))
    )
    (comp (ref "R27")
      (value "10K")
      (footprint "eagle-import:R0402")
      (libsource (lib "eagle-import") (part "R-EU_R0402"))
    )
    (comp (ref "R28")
      (value "4.7K")
      (footprint "eagle-import:R0402")
      (libsource (lib "eagle-import") (part "R-EU_R0402"))
    )
    (comp (ref "R29")
      (value "0.1R")
      (footprint "eagle-import:R0805")
      (libsource (lib "eagle-import") (part "R-EU_R0805"))
    )
    (comp (ref "R30")
      (value "0.1R")
      (footprint "eagle-import:R0805")
      (libsource (lib "eagle-import") (part "R-EU_R0805"))
    )
    (comp (ref "R31")
      (value "10K")
      (footprint "eagle-import:R0402")
      (libsource (lib "eagle-import") (part "R-EU_R0402"))
    )
    (comp (ref "R32")
      (value "4.7K")
      (footprint "eagle-import:R0402")
      (libsource (lib "eagle-import") (part "R-EU_R0402"))
    )
    (comp (ref "R33")
      (value "4.7K")
      (footprint "eagle-import:R0402")
      (libsource (lib "eagle-import") (part "R-EU_R0402"))
    )
    (comp (ref "R34")
      (value "4.7K")
      (footprint "eagle-import:R0402")
      (libsource (lib "eagle-import") (part "R-EU_R0402"))
    )
    (comp (ref "R35")
      (value "10K")
      (footprint "eagle-import:R0402")
      (libsource (lib "eagle-import") (part "R-EU_R0402"))
    )
    (comp (ref "R36")
      (value "4.7K")
      (footprint "eagle-import:R0402")
      (libsource (lib "eagle-import") (part "R-EU_R0402"))
    )
    (comp (ref "R37")
      (value "10K")
      (footprint "eagle-import:R0402")
      (libsource (lib "eagle-import") (part "R-EU_R0402"))
    )
    (comp (ref "R38")
      (value "10K")
      (footprint "eagle-import:R0402")
      (libsource (lib "eagle-import") (part "R-EU_R0402"))
    )
    (comp (ref "R39")
      (value "10K")
      (footprint "eagle-import:R0402")
      (libsource (lib "eagle-import") (part "R-EU_R0402"))
    )
    (comp (ref "R40")
      (value "10K")
      (footprint "eagle-import:R0402")
      (libsource (lib "eagle-import") (part "R-EU_R0402"))
    )
    (comp (ref "R41")
      (value "10K")
      (footprint "eagle-import:R0402")
      (libsource (lib "eagle-import") (part "R-EU_R0402"))
    )
    (comp (ref "R42")
      (value "120K")
      (footprint "eagle-import:R0402")
      (libsource (lib "eagle-import") (part "R-EU_R0402"))
    )
    (comp (ref "R43")
      (value "10K")
      (footprint "eagle-import:R0402")
      (libsource (lib "eagle-import") (part "R-EU_R0402"))
    )
    (comp (ref "R44")
      (value "39K")
      (footprint "eagle-import:R0402")
      (libsource (lib "eagle-import") (part "R-EU_R0402"))
    )
    (comp (ref "R45")
      (value "4.7K")
      (footprint "eagle-import:R0402")
      (libsource (lib "eagle-import") (part "R-EU_R0402"))
    )
    (comp (ref "R46")
      (value "4.7K")
      (footprint "eagle-import:R0402")
      (libsource (lib "eagle-import") (part "R-EU_R0402"))
    )
    (comp (ref "R47")
      (value "4.7K")
      (footprint "eagle-import:R0402")
      (libsource (lib "eagle-import") (part "R-EU_R0402"))
    )
    (comp (ref "R48")
      (value "4.7K")
      (footprint "eagle-import:R0402")
      (libsource (lib "eagle-import") (part "R-EU_R0402"))
    )
    (comp (ref "R49")
      (value "10K")
      (footprint "eagle-import:R0402")
      (libsource (lib "eagle-import") (part "R-EU_R0402"))
    )
    (comp (ref "R50")
      (value "10K")
      (footprint "eagle-import:R0402")
      (libsource (lib "eagle-import") (part "R-EU_R0402"))
    )
    (comp (ref "R51")
      (value "4.7K")
      (footprint "eagle-import:R0402")
      (libsource (lib "eagle-import") (part "R-EU_R0402"))
    )
    (comp (ref "R52")
      (value "2.2R")
      (footprint "eagle-import:R0402")
      (libsource (lib "eagle-import") (part "R-EU_R0402"))
    )
    (comp (ref "R53")
      (value "2.2R")
      (footprint "eagle-import:R0402")
      (libsource (lib "eagle-import") (part "R-EU_R0402"))
    )
    (comp (ref "R54")
      (value "4.7K")
      (footprint "eagle-import:R0402")
      (libsource (lib "eagle-import") (part "R-EU_R0402"))
    )
    (comp (ref "R55")
      (value "4.7K")
      (footprint "eagle-import:R0402")
      (libsource (lib "eagle-import") (part "R-EU_R0402"))
    )
    (comp (ref "R56")
      (value "4.7K")
      (footprint "eagle-import:R0402")
      (libsource (lib "eagle-import") (part "R-EU_R0402"))
    )
    (comp (ref "R57")
      (value "4.7K")
      (footprint "eagle-import:R0402")
      (libsource (lib "eagle-import") (part "R-EU_R0402"))
    )
    (comp (ref "R58")
      (value "10K")
      (footprint "eagle-import:R0402")
      (libsource (lib "eagle-import") (part "R-EU_R0402"))
    )
    (comp (ref "R59")
      (value "2.2R")
      (footprint "eagle-import:R0402")
      (libsource (lib "eagle-import") (part "R-EU_R0402"))
    )
    (comp (ref "R60")
      (value "10K")
      (footprint "eagle-import:R0402")
      (libsource (lib "eagle-import") (part "R-EU_R0402"))
    )
    (comp (ref "R61")
      (value "4.7K")
      (footprint "eagle-import:R0402")
      (libsource (lib "eagle-import") (part "R-EU_R0402"))
    )
    (comp (ref "R62")
      (value "4.7K")
      (footprint "eagle-import:R0402")
      (libsource (lib "eagle-import") (part "R-EU_R0402"))
    )
    (comp (ref "R63")
      (value "4.7K")
      (footprint "eagle-import:R0402")
      (libsource (lib "eagle-import") (part "R-EU_R0402"))
    )
    (comp (ref "R64")
      (value "4.7K")
      (footprint "eagle-import:R0402")
      (libsource (lib "eagle-import") (part "R-EU_R0402"))
    )
    (comp (ref "R65")
      (value "4.7K")
      (footprint "eagle-import:R0402")
      (libsource (lib "eagle-import") (part "R-EU_R0402"))
    )
    (comp (ref "R66")
      (value "4.7K")
      (footprint "eagle-import:R0402")
      (libsource (lib "eagle-import") (part "R-EU_R0402"))
    )
    (comp (ref "R70")
      (value "2.2R")
      (footprint "eagle-import:R0402")
      (libsource (lib "eagle-import") (part "R-EU_R0402"))
    )
    (comp (ref "R71")
      (value "2.2R")
      (footprint "eagle-import:R0402")
      (libsource (lib "eagle-import") (part "R-EU_R0402"))
    )
    (comp (ref "U$4")
      (value "CC-BY-SA")
      (footprint "eagle-import:CC-BY-SA")
      (libsource (lib "eagle-import") (part "CC-BY-SA"))
    )
    (comp (ref "U1")
      (value "SN74AHC595PW")
      (footprint "eagle-import:SOP65P640X120-16N")
      (libsource (lib "eagle-import") (part "SN74AHC595PW"))
    )
    (comp (ref "U2")
      (value "SN74AHC595PW")
      (footprint "eagle-import:SOP65P640X120-16N")
      (libsource (lib "eagle-import") (part "SN74AHC595PW"))
    )
    (comp (ref "U3")
      (value "SN74AHC595PW")
      (footprint "eagle-import:SOP65P640X120-16N")
      (libsource (lib "eagle-import") (part "SN74AHC595PW"))
    )
    (comp (ref "U4")
      (value "SN74AHC595PW")
      (footprint "eagle-import:SOP65P640X120-16N")
      (libsource (lib "eagle-import") (part "SN74AHC595PW"))
    )
    (comp (ref "U5")
      (value "SN74AHC595PW")
      (footprint "eagle-import:SOP65P640X120-16N")
      (libsource (lib "eagle-import") (part "SN74AHC595PW"))
    )
    (comp (ref "U6")
      (value "RT8268")
      (footprint "eagle-import:MSOP10")
      (libsource (lib "eagle-import") (part "RT8268"))
    )
    (comp (ref "U10")
      (value "RT8268")
      (footprint "eagle-import:MSOP10")
      (libsource (lib "eagle-import") (part "RT8268"))
    )
    (comp (ref "U11")
      (value "PCA9685PW")
      (footprint "eagle-import:SOP65P640X110-28N")
      (libsource (lib "eagle-import") (part "PCA9685PW"))
    )
    (comp (ref "U18")
      (value "CAT24C256")
      (footprint "eagle-import:SOIC127P600X175-8N")
      (libsource (lib "eagle-import") (part "CAT24C256"))
    )
    (comp (ref "U19")
      (value "CD4050BD")
      (footprint "eagle-import:SOIC127P600X175-16N")
      (libsource (lib "eagle-import") (part "CD4050BD"))
    )
    (comp (ref "X1")
      (value "22-05-7038-03")
      (footprint "eagle-import:7395-03")
      (libsource (lib "eagle-import") (part "22-?-0305-7038"))
    )
    (comp (ref "X2")
      (value "MSTBA4")
      (footprint "eagle-import:MSTBA4")
      (fields (field (name "MF") "FARNELL") (field (name "MPN") "1757268"))
      (libsource (lib "eagle-import") (part "MSTBA4"))
    )
    (comp (ref "X3")
      (value "MSTBA2")
      (footprint "eagle-import:MSTBA2")
      (fields (field (name "MF") "FARNELL") (field (name "MPN") "1757242"))
      (libsource (lib "eagle-import") (part "MSTBA2"))
    )
    (comp (ref "X4")
      (value "22-05-7028-02")
      (footprint "eagle-import:7395-02")
      (libsource (lib "eagle-import") (part "22-?-0205-7028"))
    )
    (comp (ref "X5")
      (value "22-05-7028-02")
      (footprint "eagle-import:7395-02")
      (libsource (lib "eagle-import") (part "22-?-0205-7028"))
    )
    (comp (ref "X6")
      (value "22-05-7028-02")
      (footprint "eagle-import:7395-02")
      (libsource (lib "eagle-import") (part "22-?-0205-7028"))
    )
    (comp (ref "X7")
      (value "22-05-7028-02")
      (footprint "eagle-import:7395-02")
      (libsource (lib "eagle-import") (part "22-?-0205-7028"))
    )
    (comp (ref "X8")
      (value "22-05-7028-02")
      (footprint "eagle-import:7395-02")
      (libsource (lib "eagle-import") (part "22-?-0205-7028"))
    )
    (comp (ref "X9")
      (value "22-05-7028-02")
      (footprint "eagle-import:7395-02")
      (libsource (lib "eagle-import") (part "22-?-0205-7028"))
    )
    (comp (ref "X10")
      (value "22-05-7038-03")
      (footprint "eagle-import:7395-03")
      (libsource (lib "eagle-import") (part "22-?-0305-7038"))
    )
    (comp (ref "X11")
      (value "22-05-7028-02")
      (footprint "eagle-import:7395-02")
      (libsource (lib "eagle-import") (part "22-?-0205-7028"))
    )
    (comp (ref "X12")
      (value "22-05-7048-04")
      (footprint "eagle-import:7395-04")
      (libsource (lib "eagle-import") (part "22-?-0405-7048"))
    )
    (comp (ref "X13")
      (value "22-05-7038-03")
      (footprint "eagle-import:7395-03")
      (libsource (lib "eagle-import") (part "22-?-0305-7038"))
    )
    (comp (ref "X14")
      (value "22-05-7048-04")
      (footprint "eagle-import:7395-04")
      (libsource (lib "eagle-import") (part "22-?-0405-7048"))
    )
    (comp (ref "X15")
      (value "22-05-7048-04")
      (footprint "eagle-import:7395-04")
      (libsource (lib "eagle-import") (part "22-?-0405-7048"))
    )
    (comp (ref "X16")
      (value "22-05-7048-04")
      (footprint "eagle-import:7395-04")
      (libsource (lib "eagle-import") (part "22-?-0405-7048"))
    )
    (comp (ref "X17")
      (value "22-05-7048-04")
      (footprint "eagle-import:7395-04")
      (libsource (lib "eagle-import") (part "22-?-0405-7048"))
    )
    (comp (ref "X18")
      (value "22-05-7048-04")
      (footprint "eagle-import:7395-04")
      (libsource (lib "eagle-import") (part "22-?-0405-7048"))
    )
    (comp (ref "X19")
      (value "22-05-7038-03")
      (footprint "eagle-import:7395-03")
      (libsource (lib "eagle-import") (part "22-?-0305-7038"))
    )
    (comp (ref "X20")
      (value "MSTBA4")
      (footprint "eagle-import:MSTBA4")
      (fields (field (name "MF") "FARNELL") (field (name "MPN") "1757268"))
      (libsource (lib "eagle-import") (part "MSTBA4"))
    )
    (comp (ref "X21")
      (value "MSTBA2")
      (footprint "eagle-import:MSTBA2")
      (fields (field (name "MF") "FARNELL") (field (name "MPN") "1757242"))
      (libsource (lib "eagle-import") (part "MSTBA2"))
    )
    (comp (ref "X22")
      (value "22-05-7038-03")
      (footprint "eagle-import:7395-03")
      (libsource (lib "eagle-import") (part "22-?-0305-7038"))
    )
    (comp (ref "X23")
      (value "22-05-7038-03")
      (footprint "eagle-import:7395-03")
      (libsource (lib "eagle-import") (part "22-?-0305-7038"))
    )
  )
  (nets
    (net (code "1") (name "+3V3") (class "Default")
      (node (ref "3.3V") (pin "TP") (pinfunction "TP_TP") (pintype "input"))
      (node (ref "C13") (pin "1") (pinfunction "1_1") (pintype "passive"))
      (node (ref "C14") (pin "1") (pinfunction "1_1") (pintype "passive"))
      (node (ref "C15") (pin "1") (pinfunction "1_1") (pintype "passive"))
      (node (ref "C2") (pin "1") (pinfunction "1_1") (pintype "passive"))
      (node (ref "C23") (pin "1") (pinfunction "1_1") (pintype "passive"))
      (node (ref "C30") (pin "1") (pinfunction "1_1") (pintype "passive"))
      (node (ref "C41") (pin "1") (pinfunction "1_1") (pintype "passive"))
      (node (ref "C42") (pin "1") (pinfunction "1_1") (pintype "passive"))
      (node (ref "C44") (pin "1") (pinfunction "1_1") (pintype "passive"))
      (node (ref "C5") (pin "1") (pinfunction "1_1") (pintype "passive"))
      (node (ref "C61") (pin "1") (pinfunction "1_1") (pintype "passive"))
      (node (ref "C63") (pin "1") (pinfunction "1_1") (pintype "passive"))
      (node (ref "C84") (pin "1") (pinfunction "1_1") (pintype "passive"))
      (node (ref "C85") (pin "1") (pinfunction "1_1") (pintype "passive"))
      (node (ref "C86") (pin "1") (pinfunction "1_1") (pintype "passive"))
      (node (ref "C87") (pin "1") (pinfunction "1_1") (pintype "passive"))
      (node (ref "C88") (pin "1") (pinfunction "1_1") (pintype "passive"))
      (node (ref "IC1") (pin "8") (pinfunction "VCC_IO_8") (pintype "bidirectional"))
      (node (ref "IC10") (pin "5") (pinfunction "VCC_5") (pintype "power_in"))
      (node (ref "IC11") (pin "5") (pinfunction "VCC_5") (pintype "power_in"))
      (node (ref "IC12") (pin "8") (pinfunction "VCC_IO_8") (pintype "bidirectional"))
      (node (ref "IC13") (pin "5") (pinfunction "VCC_5") (pintype "power_in"))
      (node (ref "IC14") (pin "5") (pinfunction "VCC_5") (pintype "power_in"))
      (node (ref "IC15") (pin "8") (pinfunction "VCC_IO_8") (pintype "bidirectional"))
      (node (ref "IC16") (pin "5") (pinfunction "VCC_5") (pintype "power_in"))
      (node (ref "IC17") (pin "5") (pinfunction "VCC_5") (pintype "power_in"))
      (node (ref "IC18") (pin "5") (pinfunction "VCC_5") (pintype "power_in"))
      (node (ref "IC19") (pin "5") (pinfunction "VCC_5") (pintype "power_in"))
      (node (ref "IC2") (pin "8") (pinfunction "VCC_IO_8") (pintype "bidirectional"))
      (node (ref "IC3") (pin "5") (pinfunction "VCC_5") (pintype "power_in"))
      (node (ref "IC4") (pin "5") (pinfunction "VCC_5") (pintype "power_in"))
      (node (ref "IC5") (pin "8") (pinfunction "VCC_IO_8") (pintype "bidirectional"))
      (node (ref "IC8") (pin "5") (pinfunction "VCC_5") (pintype "power_in"))
      (node (ref "IC9") (pin "5") (pinfunction "VCC_5") (pintype "power_in"))
      (node (ref "P9") (pin "3") (pinfunction "3_3") (pintype "passive"))
      (node (ref "P9") (pin "4") (pinfunction "4_4") (pintype "passive"))
      (node (ref "R23") (pin "2") (pinfunction "2_2") (pintype "passive"))
      (node (ref "R24") (pin "2") (pinfunction "2_2") (pintype "passive"))
      (node (ref "R28") (pin "2") (pinfunction "2_2") (pintype "passive"))
      (node (ref "R36") (pin "2") (pinfunction "2_2") (pintype "passive"))
      (node (ref "R51") (pin "2") (pinfunction "2_2") (pintype "passive"))
      (node (ref "R54") (pin "2") (pinfunction "2_2") (pintype "passive"))
      (node (ref "U1") (pin "10") (pinfunction "~{SRCLR}_10") (pintype "input"))
      (node (ref "U1") (pin "16") (pinfunction "VCC_16") (pintype "power_in"))
      (node (ref "U18") (pin "3") (pinfunction "A2_3") (pintype "input"))
      (node (ref "U18") (pin "8") (pinfunction "VCC_8") (pintype "power_in"))
      (node (ref "U19") (pin "1") (pinfunction "VCC_1") (pintype "power_in"))
      (node (ref "U2") (pin "10") (pinfunction "~{SRCLR}_10") (pintype "input"))
      (node (ref "U2") (pin "16") (pinfunction "VCC_16") (pintype "power_in"))
      (node (ref "U3") (pin "10") (pinfunction "~{SRCLR}_10") (pintype "input"))
      (node (ref "U3") (pin "16") (pinfunction "VCC_16") (pintype "power_in"))
      (node (ref "U4") (pin "10") (pinfunction "~{SRCLR}_10") (pintype "input"))
      (node (ref "U4") (pin "16") (pinfunction "VCC_16") (pintype "power_in"))
      (node (ref "U5") (pin "10") (pinfunction "~{SRCLR}_10") (pintype "input"))
      (node (ref "U5") (pin "16") (pinfunction "VCC_16") (pintype "power_in"))
      (node (ref "X23") (pin "1") (pinfunction "S_1") (pintype "passive"))
    )
    (net (code "2") (name "+5V") (class "Default")
      (node (ref "5V") (pin "TP") (pinfunction "TP_TP") (pintype "input"))
      (node (ref "C17") (pin "1") (pinfunction "1_1") (pintype "passive"))
      (node (ref "C48") (pin "1") (pinfunction "1_1") (pintype "passive"))
      (node (ref "C80") (pin "1") (pinfunction "1_1") (pintype "passive"))
      (node (ref "C82") (pin "1") (pinfunction "1_1") (pintype "passive"))
      (node (ref "C83") (pin "1") (pinfunction "1_1") (pintype "passive"))
      (node (ref "IC6") (pin "5") (pinfunction "VCC_5") (pintype "power_in"))
      (node (ref "IC7") (pin "5") (pinfunction "VCC_5") (pintype "power_in"))
      (node (ref "L1") (pin "P$1") (pinfunction "P$1_P$1") (pintype "passive"))
      (node (ref "P9") (pin "5") (pinfunction "5_5") (pintype "passive"))
      (node (ref "P9") (pin "6") (pinfunction "6_6") (pintype "passive"))
      (node (ref "R12") (pin "1") (pinfunction "1_1") (pintype "passive"))
      (node (ref "R61") (pin "2") (pinfunction "2_2") (pintype "passive"))
      (node (ref "R62") (pin "2") (pinfunction "2_2") (pintype "passive"))
      (node (ref "R63") (pin "2") (pinfunction "2_2") (pintype "passive"))
      (node (ref "R64") (pin "2") (pinfunction "2_2") (pintype "passive"))
      (node (ref "R65") (pin "2") (pinfunction "2_2") (pintype "passive"))
      (node (ref "R66") (pin "2") (pinfunction "2_2") (pintype "passive"))
      (node (ref "U11") (pin "1") (pinfunction "A0_1") (pintype "input"))
      (node (ref "U11") (pin "2") (pinfunction "A1_2") (pintype "input"))
      (node (ref "U11") (pin "24") (pinfunction "A5_24") (pintype "input"))
      (node (ref "U11") (pin "28") (pinfunction "VDD_28") (pintype "power_in"))
      (node (ref "U11") (pin "3") (pinfunction "A2_3") (pintype "input"))
      (node (ref "U11") (pin "4") (pinfunction "A3_4") (pintype "input"))
      (node (ref "U11") (pin "5") (pinfunction "A4_5") (pintype "input"))
      (node (ref "X1") (pin "3") (pinfunction "S_3") (pintype "passive"))
      (node (ref "X10") (pin "3") (pinfunction "S_3") (pintype "passive"))
      (node (ref "X12") (pin "3") (pinfunction "S_3") (pintype "passive"))
      (node (ref "X13") (pin "3") (pinfunction "S_3") (pintype "passive"))
      (node (ref "X19") (pin "3") (pinfunction "S_3") (pintype "passive"))
      (node (ref "X22") (pin "3") (pinfunction "S_3") (pintype "passive"))
    )
    (net (code "3") (name "/DALLAS_W1") (class "Default")
      (node (ref "P9") (pin "22") (pinfunction "22_22") (pintype "passive"))
      (node (ref "X23") (pin "2") (pinfunction "S_2") (pintype "passive"))
    )
    (net (code "4") (name "/DIR_E") (class "Default")
      (node (ref "IC12") (pin "7") (pinfunction "REFR_DIR_7") (pintype "bidirectional"))
      (node (ref "P8") (pin "15") (pinfunction "15_15") (pintype "passive"))
    )
    (net (code "5") (name "/DIR_H") (class "Default")
      (node (ref "IC15") (pin "7") (pinfunction "REFR_DIR_7") (pintype "bidirectional"))
      (node (ref "P8") (pin "16") (pinfunction "16_16") (pintype "passive"))
    )
    (net (code "6") (name "/DIR_X") (class "Default")
      (node (ref "IC1") (pin "7") (pinfunction "REFR_DIR_7") (pintype "bidirectional"))
      (node (ref "P8") (pin "26") (pinfunction "26_26") (pintype "passive"))
    )
    (net (code "7") (name "/DIR_Y") (class "Default")
      (node (ref "IC2") (pin "7") (pinfunction "REFR_DIR_7") (pintype "bidirectional"))
      (node (ref "P8") (pin "19") (pinfunction "19_19") (pintype "passive"))
    )
    (net (code "8") (name "/DIR_Z") (class "Default")
      (node (ref "IC5") (pin "7") (pinfunction "REFR_DIR_7") (pintype "bidirectional"))
      (node (ref "P8") (pin "14") (pinfunction "14_14") (pintype "passive"))
    )
    (net (code "9") (name "/ENABLE") (class "Default")
      (node (ref "P9") (pin "41") (pinfunction "41_41") (pintype "passive"))
      (node (ref "R23") (pin "1") (pinfunction "1_1") (pintype "passive"))
      (node (ref "U11") (pin "23") (pinfunction "~{OE}_23") (pintype "input"))
    )
    (net (code "10") (name "/ENABLE_EH") (class "Default")
      (node (ref "IC12") (pin "22") (pinfunction "DRV_ENN_CFG6_22") (pintype "bidirectional"))
      (node (ref "IC15") (pin "22") (pinfunction "DRV_ENN_CFG6_22") (pintype "bidirectional"))
      (node (ref "IC19") (pin "4") (pinfunction "O_4") (pintype "output"))
    )
    (net (code "11") (name "/ENABLE_XYZ") (class "Default")
      (node (ref "IC1") (pin "22") (pinfunction "DRV_ENN_CFG6_22") (pintype "bidirectional"))
      (node (ref "IC18") (pin "4") (pinfunction "O_4") (pintype "output"))
      (node (ref "IC2") (pin "22") (pinfunction "DRV_ENN_CFG6_22") (pintype "bidirectional"))
      (node (ref "IC5") (pin "22") (pinfunction "DRV_ENN_CFG6_22") (pintype "bidirectional"))
    )
    (net (code "12") (name "/END_STOP_X_1") (class "Default")
      (node (ref "P9") (pin "25") (pinfunction "25_25") (pintype "passive"))
      (node (ref "U19") (pin "2") (pinfunction "G=A_2") (pintype "output"))
    )
    (net (code "13") (name "/END_STOP_X_1_IN") (class "Default")
      (node (ref "R61") (pin "1") (pinfunction "1_1") (pintype "passive"))
      (node (ref "U19") (pin "3") (pinfunction "A_3") (pintype "input"))
      (node (ref "X22") (pin "1") (pinfunction "S_1") (pintype "passive"))
    )
    (net (code "14") (name "/END_STOP_X_2") (class "Default")
      (node (ref "P9") (pin "11") (pinfunction "11_11") (pintype "passive"))
      (node (ref "U19") (pin "10") (pinfunction "J=D_10") (pintype "output"))
    )
    (net (code "15") (name "/END_STOP_X_2_IN") (class "Default")
      (node (ref "IC6") (pin "4") (pinfunction "O_4") (pintype "output"))
      (node (ref "R64") (pin "1") (pinfunction "1_1") (pintype "passive"))
      (node (ref "U19") (pin "9") (pinfunction "D_9") (pintype "input"))
      (node (ref "X10") (pin "1") (pinfunction "S_1") (pintype "passive"))
    )
    (net (code "16") (name "/END_STOP_Y_1") (class "Default")
      (node (ref "P9") (pin "23") (pinfunction "23_23") (pintype "passive"))
      (node (ref "U19") (pin "4") (pinfunction "H=B_4") (pintype "output"))
    )
    (net (code "17") (name "/END_STOP_Y_1_IN") (class "Default")
      (node (ref "R62") (pin "1") (pinfunction "1_1") (pintype "passive"))
      (node (ref "U19") (pin "5") (pinfunction "B_5") (pintype "input"))
      (node (ref "X1") (pin "1") (pinfunction "S_1") (pintype "passive"))
    )
    (net (code "18") (name "/END_STOP_Y_2") (class "Default")
      (node (ref "P9") (pin "28") (pinfunction "28_28") (pintype "passive"))
      (node (ref "U19") (pin "12") (pinfunction "K=E_12") (pintype "output"))
    )
    (net (code "19") (name "/END_STOP_Y_2_IN") (class "Default")
      (node (ref "IC7") (pin "4") (pinfunction "O_4") (pintype "output"))
      (node (ref "R65") (pin "1") (pinfunction "1_1") (pintype "passive"))
      (node (ref "U19") (pin "11") (pinfunction "E_11") (pintype "input"))
      (node (ref "X19") (pin "1") (pinfunction "S_1") (pintype "passive"))
    )
    (net (code "20") (name "/END_STOP_Z_1") (class "Default")
      (node (ref "P9") (pin "13") (pinfunction "13_13") (pintype "passive"))
      (node (ref "U19") (pin "6") (pinfunction "I=C_6") (pintype "output"))
    )
    (net (code "21") (name "/END_STOP_Z_1_IN") (class "Default")
      (node (ref "R63") (pin "1") (pinfunction "1_1") (pintype "passive"))
      (node (ref "U19") (pin "7") (pinfunction "C_7") (pintype "input"))
      (node (ref "X13") (pin "1") (pinfunction "S_1") (pintype "passive"))
    )
    (net (code "22") (name "/END_STOP_Z_2") (class "Default")
      (node (ref "P9") (pin "18") (pinfunction "18_18") (pintype "passive"))
      (node (ref "U19") (pin "15") (pinfunction "L=F_15") (pintype "output"))
    )
    (net (code "23") (name "/END_STOP_Z_2_IN") (class "Default")
      (node (ref "R66") (pin "1") (pinfunction "1_1") (pintype "passive"))
      (node (ref "U19") (pin "14") (pinfunction "F_14") (pintype "input"))
      (node (ref "X12") (pin "1") (pinfunction "S_1") (pintype "passive"))
    )
    (net (code "24") (name "/FAN0") (class "Default")
      (node (ref "Q6") (pin "1") (pinfunction "B_1") (pintype "passive"))
      (node (ref "R34") (pin "2") (pinfunction "2_2") (pintype "passive"))
      (node (ref "U11") (pin "13") (pinfunction "LED7_13") (pintype "output"))
    )
    (net (code "25") (name "/FAN1") (class "Default")
      (node (ref "Q7") (pin "1") (pinfunction "B_1") (pintype "passive"))
      (node (ref "R33") (pin "2") (pinfunction "2_2") (pintype "passive"))
      (node (ref "U11") (pin "15") (pinfunction "LED8_15") (pintype "output"))
    )
    (net (code "26") (name "/FAN2") (class "Default")
      (node (ref "Q4") (pin "1") (pinfunction "B_1") (pintype "passive"))
      (node (ref "R32") (pin "2") (pinfunction "2_2") (pintype "passive"))
      (node (ref "U11") (pin "16") (pinfunction "LED9_16") (pintype "output"))
    )
    (net (code "27") (name "/FAN3") (class "Default")
      (node (ref "Q5") (pin "1") (pinfunction "B_1") (pintype "passive"))
      (node (ref "R5") (pin "2") (pinfunction "2_2") (pintype "passive"))
      (node (ref "U11") (pin "17") (pinfunction "LED10_17") (pintype "output"))
    )
    (net (code "28") (name "/FAULT_E") (class "Default")
      (node (ref "IC12") (pin "20") (pinfunction "SWN_DIAG0_20") (pintype "bidirectional"))
      (node (ref "P8") (pin "18") (pinfunction "18_18") (pintype "passive"))
      (node (ref "R36") (pin "1") (pinfunction "1_1") (pintype "passive"))
    )
    (net (code "29") (name "/FAULT_H") (class "Default")
      (node (ref "IC15") (pin "20") (pinfunction "SWN_DIAG0_20") (pintype "bidirectional"))
      (node (ref "P8") (pin "8") (pinfunction "8_8") (pintype "passive"))
      (node (ref "R51") (pin "1") (pinfunction "1_1") (pintype "passive"))
    )
    (net (code "30") (name "/FAULT_X") (class "Default")
      (node (ref "IC1") (pin "20") (pinfunction "SWN_DIAG0_20") (pintype "bidirectional"))
      (node (ref "P8") (pin "10") (pinfunction "10_10") (pintype "passive"))
      (node (ref "R54") (pin "1") (pinfunction "1_1") (pintype "passive"))
    )
    (net (code "31") (name "/FAULT_Y") (class "Default")
      (node (ref "IC2") (pin "20") (pinfunction "SWN_DIAG0_20") (pintype "bidirectional"))
      (node (ref "P8") (pin "9") (pinfunction "9_9") (pintype "passive"))
      (node (ref "R24") (pin "1") (pinfunction "1_1") (pintype "passive"))
    )
    (net (code "32") (name "/FAULT_Z") (class "Default")
      (node (ref "IC5") (pin "20") (pinfunction "SWN_DIAG0_20") (pintype "bidirectional"))
      (node (ref "P9") (pin "24") (pinfunction "24_24") (pintype "passive"))
      (node (ref "R28") (pin "1") (pinfunction "1_1") (pintype "passive"))
    )
    (net (code "33") (name "/HEATER_E") (class "Default")
      (node (ref "Q3") (pin "4") (pinfunction "G_4") (pintype "passive"))
      (node (ref "R47") (pin "2") (pinfunction "2_2") (pintype "passive"))
      (node (ref "U11") (pin "11") (pinfunction "LED5_11") (pintype "output"))
    )
    (net (code "34") (name "/HEATER_H") (class "Default")
      (node (ref "Q2") (pin "4") (pinfunction "G_4") (pintype "passive"))
      (node (ref "R48") (pin "2") (pinfunction "2_2") (pintype "passive"))
      (node (ref "U11") (pin "9") (pinfunction "LED3_9") (pintype "output"))
    )
    (net (code "35") (name "/HEATER_HBP") (class "Default")
      (node (ref "Q1") (pin "4") (pinfunction "G_4") (pintype "passive"))
      (node (ref "R46") (pin "2") (pinfunction "2_2") (pintype "passive"))
      (node (ref "U11") (pin "10") (pinfunction "LED4_10") (pintype "output"))
    )
    (net (code "36") (name "/I2C2_SCL") (class "Default")
      (node (ref "P9") (pin "19") (pinfunction "19_19") (pintype "passive"))
      (node (ref "U11") (pin "26") (pinfunction "SCL_26") (pintype "input"))
      (node (ref "U18") (pin "6") (pinfunction "SCL_6") (pintype "input"))
    )
    (net (code "37") (name "/I2C2_SDA") (class "Default")
      (node (ref "P9") (pin "20") (pinfunction "20_20") (pintype "passive"))
      (node (ref "U11") (pin "27") (pinfunction "SDA_27") (pintype "bidirectional"))
      (node (ref "U18") (pin "5") (pinfunction "SDA_5") (pintype "bidirectional"))
    )
    (net (code "38") (name "/IREF_E_RAW") (class "Default")
      (node (ref "R60") (pin "2") (pinfunction "2_2") (pintype "passive"))
      (node (ref "U11") (pin "21") (pinfunction "LED14_21") (pintype "output"))
    )
    (net (code "39") (name "/IREF_H_RAW") (class "Default")
      (node (ref "R31") (pin "2") (pinfunction "2_2") (pintype "passive"))
      (node (ref "U11") (pin "22") (pinfunction "LED15_22") (pintype "output"))
    )
    (net (code "40") (name "/IREF_X_RAW") (class "Default")
      (node (ref "R41") (pin "2") (pinfunction "2_2") (pintype "passive"))
      (node (ref "U11") (pin "18") (pinfunction "LED11_18") (pintype "output"))
    )
    (net (code "41") (name "/IREF_Y_RAW") (class "Default")
      (node (ref "R37") (pin "2") (pinfunction "2_2") (pintype "passive"))
      (node (ref "U11") (pin "19") (pinfunction "LED12_19") (pintype "output"))
    )
    (net (code "42") (name "/IREF_Z_RAW") (class "Default")
      (node (ref "R58") (pin "2") (pinfunction "2_2") (pintype "passive"))
      (node (ref "U11") (pin "20") (pinfunction "LED13_20") (pintype "output"))
    )
    (net (code "43") (name "/SERVO_0") (class "Default")
      (node (ref "IC6") (pin "2") (pinfunction "I_2") (pintype "input"))
      (node (ref "P9") (pin "14") (pinfunction "14_14") (pintype "passive"))
    )
    (net (code "44") (name "/SERVO_0_EN") (class "Default")
      (node (ref "IC6") (pin "1") (pinfunction "OE_1") (pintype "input"))
      (node (ref "U2") (pin "15") (pinfunction "QA_15") (pintype "output"))
    )
    (net (code "45") (name "/SERVO_1") (class "Default")
      (node (ref "IC7") (pin "2") (pinfunction "I_2") (pintype "input"))
      (node (ref "P9") (pin "16") (pinfunction "16_16") (pintype "passive"))
    )
    (net (code "46") (name "/SERVO_1_EN") (class "Default")
      (node (ref "IC7") (pin "1") (pinfunction "OE_1") (pintype "input"))
      (node (ref "U3") (pin "15") (pinfunction "QA_15") (pintype "output"))
    )
    (net (code "47") (name "/SER_2") (class "Default")
      (node (ref "U1") (pin "9") (pinfunction "QH_2_9") (pintype "output"))
      (node (ref "U2") (pin "14") (pinfunction "SER_14") (pintype "input"))
    )
    (net (code "48") (name "/SER_3") (class "Default")
      (node (ref "U2") (pin "9") (pinfunction "QH_2_9") (pintype "output"))
      (node (ref "U3") (pin "14") (pinfunction "SER_14") (pintype "input"))
    )
    (net (code "49") (name "/SER_4") (class "Default")
      (node (ref "U3") (pin "9") (pinfunction "QH_2_9") (pintype "output"))
      (node (ref "U4") (pin "14") (pinfunction "SER_14") (pintype "input"))
    )
    (net (code "50") (name "/SER_5") (class "Default")
      (node (ref "U4") (pin "9") (pinfunction "QH_2_9") (pintype "output"))
      (node (ref "U5") (pin "14") (pinfunction "SER_14") (pintype "input"))
    )
    (net (code "51") (name "/SPI1_CS1") (class "Default")
      (node (ref "P9") (pin "42") (pinfunction "42_42") (pintype "passive"))
      (node (ref "U1") (pin "12") (pinfunction "RCLK_12") (pintype "input"))
      (node (ref "U2") (pin "12") (pinfunction "RCLK_12") (pintype "input"))
      (node (ref "U3") (pin "12") (pinfunction "RCLK_12") (pintype "input"))
      (node (ref "U4") (pin "12") (pinfunction "RCLK_12") (pintype "input"))
      (node (ref "U5") (pin "12") (pinfunction "RCLK_12") (pintype "input"))
    )
    (net (code "52") (name "/SPI1_MOSI") (class "Default")
      (node (ref "P9") (pin "30") (pinfunction "30_30") (pintype "passive"))
      (node (ref "U1") (pin "14") (pinfunction "SER_14") (pintype "input"))
    )
    (net (code "53") (name "/SPI1_SCLK") (class "Default")
      (node (ref "P9") (pin "31") (pinfunction "31_31") (pintype "passive"))
      (node (ref "U1") (pin "11") (pinfunction "SRCLK_11") (pintype "input"))
      (node (ref "U2") (pin "11") (pinfunction "SRCLK_11") (pintype "input"))
      (node (ref "U3") (pin "11") (pinfunction "SRCLK_11") (pintype "input"))
      (node (ref "U4") (pin "11") (pinfunction "SRCLK_11") (pintype "input"))
      (node (ref "U5") (pin "11") (pinfunction "SRCLK_11") (pintype "input"))
    )
    (net (code "54") (name "/STEP_E") (class "Default")
      (node (ref "IC12") (pin "6") (pinfunction "REFL_STEP_6") (pintype "bidirectional"))
      (node (ref "P9") (pin "12") (pinfunction "12_12") (pintype "passive"))
    )
    (net (code "55") (name "/STEP_H") (class "Default")
      (node (ref "IC15") (pin "6") (pinfunction "REFL_STEP_6") (pintype "bidirectional"))
      (node (ref "P8") (pin "11") (pinfunction "11_11") (pintype "passive"))
    )
    (net (code "56") (name "/STEP_X") (class "Default")
      (node (ref "IC1") (pin "6") (pinfunction "REFL_STEP_6") (pintype "bidirectional"))
      (node (ref "P8") (pin "17") (pinfunction "17_17") (pintype "passive"))
    )
    (net (code "57") (name "/STEP_Y") (class "Default")
      (node (ref "IC2") (pin "6") (pinfunction "REFL_STEP_6") (pintype "bidirectional"))
      (node (ref "P8") (pin "12") (pinfunction "12_12") (pintype "passive"))
    )
    (net (code "58") (name "/STEP_Z") (class "Default")
      (node (ref "IC5") (pin "6") (pinfunction "REFL_STEP_6") (pintype "bidirectional"))
      (node (ref "P8") (pin "13") (pinfunction "13_13") (pintype "passive"))
    )
    (net (code "59") (name "/TERM_EXT1") (class "Default")
      (node (ref "C26") (pin "1") (pinfunction "1_1") (pintype "passive"))
      (node (ref "P9") (pin "33") (pinfunction "33_33") (pintype "passive"))
      (node (ref "R38") (pin "2") (pinfunction "2_2") (pintype "passive"))
    )
    (net (code "60") (name "/TERM_EXT2") (class "Default")
      (node (ref "C46") (pin "1") (pinfunction "1_1") (pintype "passive"))
      (node (ref "P9") (pin "36") (pinfunction "36_36") (pintype "passive"))
      (node (ref "R40") (pin "2") (pinfunction "2_2") (pintype "passive"))
    )
    (net (code "61") (name "/TERM_HBP") (class "Default")
      (node (ref "C45") (pin "1") (pinfunction "1_1") (pintype "passive"))
      (node (ref "P9") (pin "35") (pinfunction "35_35") (pintype "passive"))
      (node (ref "R39") (pin "2") (pinfunction "2_2") (pintype "passive"))
    )
    (net (code "62") (name "/TRISTATE_STEPPERS") (class "Default")
      (node (ref "IC18") (pin "1") (pinfunction "OE_1") (pintype "input"))
      (node (ref "IC19") (pin "1") (pinfunction "OE_1") (pintype "input"))
      (node (ref "U5") (pin "15") (pinfunction "QA_15") (pintype "output"))
    )
    (net (code "63") (name "/VDD_12V") (class "Default")
      (node (ref "12V") (pin "TP") (pinfunction "TP_TP") (pintype "input"))
      (node (ref "C53") (pin "1") (pinfunction "1_1") (pintype "passive"))
      (node (ref "C81") (pin "1") (pinfunction "1_1") (pintype "passive"))
      (node (ref "L2") (pin "P$1") (pinfunction "P$1_P$1") (pintype "passive"))
      (node (ref "R11") (pin "2") (pinfunction "2_2") (pintype "passive"))
      (node (ref "R19") (pin "2") (pinfunction "2_2") (pintype "passive"))
      (node (ref "R20") (pin "2") (pinfunction "2_2") (pintype "passive"))
      (node (ref "R21") (pin "2") (pinfunction "2_2") (pintype "passive"))
      (node (ref "R25") (pin "2") (pinfunction "2_2") (pintype "passive"))
      (node (ref "R42") (pin "1") (pinfunction "1_1") (pintype "passive"))
      (node (ref "X12") (pin "4") (pinfunction "S_4") (pintype "passive"))
      (node (ref "X4") (pin "1") (pinfunction "S_1") (pintype "passive"))
      (node (ref "X5") (pin "1") (pinfunction "S_1") (pintype "passive"))
      (node (ref "X6") (pin "1") (pinfunction "S_1") (pintype "passive"))
      (node (ref "X9") (pin "1") (pinfunction "S_1") (pintype "passive"))
    )
    (net (code "64") (name "/VDD_ADC") (class "Default")
      (node (ref "P9") (pin "32") (pinfunction "32_32") (pintype "passive"))
      (node (ref "R13") (pin "2") (pinfunction "2_2") (pintype "passive"))
      (node (ref "R17") (pin "2") (pinfunction "2_2") (pintype "passive"))
      (node (ref "R18") (pin "2") (pinfunction "2_2") (pintype "passive"))
    )
    (net (code "65") (name "/VDD_IN") (class "Default")
      (node (ref "12..24V") (pin "TP") (pinfunction "TP_TP") (pintype "input"))
      (node (ref "C10") (pin "1") (pinfunction "1_1") (pintype "passive"))
      (node (ref "C11") (pin "1") (pinfunction "1_1") (pintype "passive"))
      (node (ref "C16") (pin "1") (pinfunction "1_1") (pintype "passive"))
      (node (ref "C19") (pin "1") (pinfunction "1_1") (pintype "passive"))
      (node (ref "C20") (pin "2") (pinfunction "2_2") (pintype "passive"))
      (node (ref "C22") (pin "2") (pinfunction "2_2") (pintype "passive"))
      (node (ref "C24") (pin "1") (pinfunction "1_1") (pintype "passive"))
      (node (ref "C27") (pin "1") (pinfunction "1_1") (pintype "passive"))
      (node (ref "C28") (pin "2") (pinfunction "2_2") (pintype "passive"))
      (node (ref "C29") (pin "1") (pinfunction "1_1") (pintype "passive"))
      (node (ref "C31") (pin "1") (pinfunction "1_1") (pintype "passive"))
      (node (ref "C32") (pin "2") (pinfunction "2_2") (pintype "passive"))
      (node (ref "C34") (pin "1") (pinfunction "1_1") (pintype "passive"))
      (node (ref "C35") (pin "2") (pinfunction "2_2") (pintype "passive"))
      (node (ref "C38") (pin "2") (pinfunction "2_2") (pintype "passive"))
      (node (ref "C4") (pin "1") (pinfunction "1_1") (pintype "passive"))
      (node (ref "C40") (pin "1") (pinfunction "1_1") (pintype "passive"))
      (node (ref "C43") (pin "1") (pinfunction "1_1") (pintype "passive"))
      (node (ref "C47") (pin "1") (pinfunction "1_1") (pintype "passive"))
      (node (ref "C52") (pin "1") (pinfunction "1_1") (pintype "passive"))
      (node (ref "C6") (pin "1") (pinfunction "1_1") (pintype "passive"))
      (node (ref "C60") (pin "1") (pinfunction "1_1") (pintype "passive"))
      (node (ref "C64") (pin "2") (pinfunction "2_2") (pintype "passive"))
      (node (ref "C66") (pin "2") (pinfunction "2_2") (pintype "passive"))
      (node (ref "C67") (pin "2") (pinfunction "2_2") (pintype "passive"))
      (node (ref "C69") (pin "2") (pinfunction "2_2") (pintype "passive"))
      (node (ref "C8") (pin "1") (pinfunction "1_1") (pintype "passive"))
      (node (ref "D1") (pin "C") (pinfunction "C_C") (pintype "passive"))
      (node (ref "D2") (pin "C") (pinfunction "C_C") (pintype "passive"))
      (node (ref "D3") (pin "C") (pinfunction "C_C") (pintype "passive"))
      (node (ref "D5") (pin "C") (pinfunction "C_C") (pintype "passive"))
      (node (ref "F1") (pin "P$3") (pinfunction "2_P$3") (pintype "passive"))
      (node (ref "F1") (pin "P$4") (pinfunction "2_P$4") (pintype "passive"))
      (node (ref "IC1") (pin "16") (pinfunction "VS_16") (pintype "bidirectional"))
      (node (ref "IC1") (pin "30") (pinfunction "VSA_30") (pintype "bidirectional"))
      (node (ref "IC1") (pin "31") (pinfunction "VS_31") (pintype "bidirectional"))
      (node (ref "IC12") (pin "16") (pinfunction "VS_16") (pintype "bidirectional"))
      (node (ref "IC12") (pin "30") (pinfunction "VSA_30") (pintype "bidirectional"))
      (node (ref "IC12") (pin "31") (pinfunction "VS_31") (pintype "bidirectional"))
      (node (ref "IC15") (pin "16") (pinfunction "VS_16") (pintype "bidirectional"))
      (node (ref "IC15") (pin "30") (pinfunction "VSA_30") (pintype "bidirectional"))
      (node (ref "IC15") (pin "31") (pinfunction "VS_31") (pintype "bidirectional"))
      (node (ref "IC2") (pin "16") (pinfunction "VS_16") (pintype "bidirectional"))
      (node (ref "IC2") (pin "30") (pinfunction "VSA_30") (pintype "bidirectional"))
      (node (ref "IC2") (pin "31") (pinfunction "VS_31") (pintype "bidirectional"))
      (node (ref "IC5") (pin "16") (pinfunction "VS_16") (pintype "bidirectional"))
      (node (ref "IC5") (pin "30") (pinfunction "VSA_30") (pintype "bidirectional"))
      (node (ref "IC5") (pin "31") (pinfunction "VS_31") (pintype "bidirectional"))
      (node (ref "R14") (pin "2") (pinfunction "2_2") (pintype "passive"))
      (node (ref "R15") (pin "2") (pinfunction "2_2") (pintype "passive"))
      (node (ref "R16") (pin "2") (pinfunction "2_2") (pintype "passive"))
      (node (ref "R45") (pin "1") (pinfunction "1_1") (pintype "passive"))
      (node (ref "R55") (pin "2") (pinfunction "2_2") (pintype "passive"))
      (node (ref "R56") (pin "2") (pinfunction "2_2") (pintype "passive"))
      (node (ref "R57") (pin "2") (pinfunction "2_2") (pintype "passive"))
      (node (ref "U10") (pin "4") (pinfunction "VIN_4") (pintype "power_in"))
      (node (ref "U6") (pin "4") (pinfunction "VIN_4") (pintype "power_in"))
      (node (ref "X20") (pin "1") (pinfunction "1_1") (pintype "passive"))
      (node (ref "X20") (pin "2") (pinfunction "1_2") (pintype "passive"))
      (node (ref "X21") (pin "1") (pinfunction "1_1") (pintype "passive"))
      (node (ref "X3") (pin "1") (pinfunction "1_1") (pintype "passive"))
    )
    (net (code "66") (name "/VIN") (class "Default")
      (node (ref "F1") (pin "P$1") (pinfunction "1_P$1") (pintype "passive"))
      (node (ref "F1") (pin "P$2") (pinfunction "1_P$2") (pintype "passive"))
      (node (ref "LED8") (pin "A") (pinfunction "A_A") (pintype "passive"))
      (node (ref "X2") (pin "3") (pinfunction "1_3") (pintype "passive"))
      (node (ref "X2") (pin "4") (pinfunction "1_4") (pintype "passive"))
    )
    (net (code "67") (name "GND") (class "Default")
      (node (ref "C10") (pin "2") (pinfunction "2_2") (pintype "passive"))
      (node (ref "C11") (pin "2") (pinfunction "2_2") (pintype "passive"))
      (node (ref "C12") (pin "2") (pinfunction "2_2") (pintype "passive"))
      (node (ref "C13") (pin "2") (pinfunction "2_2") (pintype "passive"))
      (node (ref "C14") (pin "2") (pinfunction "2_2") (pintype "passive"))
      (node (ref "C15") (pin "2") (pinfunction "2_2") (pintype "passive"))
      (node (ref "C16") (pin "2") (pinfunction "2_2") (pintype "passive"))
      (node (ref "C17") (pin "2") (pinfunction "2_2") (pintype "passive"))
      (node (ref "C18") (pin "2") (pinfunction "2_2") (pintype "passive"))
      (node (ref "C19") (pin "2") (pinfunction "2_2") (pintype "passive"))
      (node (ref "C2") (pin "2") (pinfunction "2_2") (pintype "passive"))
      (node (ref "C20") (pin "1") (pinfunction "1_1") (pintype "passive"))
      (node (ref "C21") (pin "1") (pinfunction "1_1") (pintype "passive"))
      (node (ref "C23") (pin "2") (pinfunction "2_2") (pintype "passive"))
      (node (ref "C24") (pin "2") (pinfunction "2_2") (pintype "passive"))
      (node (ref "C25") (pin "2") (pinfunction "2_2") (pintype "passive"))
      (node (ref "C26") (pin "2") (pinfunction "2_2") (pintype "passive"))
      (node (ref "C27") (pin "2") (pinfunction "2_2") (pintype "passive"))
      (node (ref "C28") (pin "1") (pinfunction "1_1") (pintype "passive"))
      (node (ref "C29") (pin "2") (pinfunction "2_2") (pintype "passive"))
      (node (ref "C30") (pin "2") (pinfunction "2_2") (pintype "passive"))
      (node (ref "C31") (pin "2") (pinfunction "2_2") (pintype "passive"))
      (node (ref "C32") (pin "1") (pinfunction "1_1") (pintype "passive"))
      (node (ref "C33") (pin "1") (pinfunction "1_1") (pintype "passive"))
      (node (ref "C34") (pin "2") (pinfunction "2_2") (pintype "passive"))
      (node (ref "C36") (pin "2") (pinfunction "2_2") (pintype "passive"))
      (node (ref "C37") (pin "1") (pinfunction "1_1") (pintype "passive"))
      (node (ref "C4") (pin "2") (pinfunction "2_2") (pintype "passive"))
      (node (ref "C40") (pin "2") (pinfunction "2_2") (pintype "passive"))
      (node (ref "C41") (pin "2") (pinfunction "2_2") (pintype "passive"))
      (node (ref "C42") (pin "2") (pinfunction "2_2") (pintype "passive"))
      (node (ref "C43") (pin "2") (pinfunction "2_2") (pintype "passive"))
      (node (ref "C44") (pin "2") (pinfunction "2_2") (pintype "passive"))
      (node (ref "C45") (pin "2") (pinfunction "2_2") (pintype "passive"))
      (node (ref "C46") (pin "2") (pinfunction "2_2") (pintype "passive"))
      (node (ref "C47") (pin "2") (pinfunction "2_2") (pintype "passive"))
      (node (ref "C48") (pin "2") (pinfunction "2_2") (pintype "passive"))
      (node (ref "C49") (pin "2") (pinfunction "2_2") (pintype "passive"))
      (node (ref "C5") (pin "2") (pinfunction "2_2") (pintype "passive"))
      (node (ref "C52") (pin "2") (pinfunction "2_2") (pintype "passive"))
      (node (ref "C53") (pin "2") (pinfunction "2_2") (pintype "passive"))
      (node (ref "C54") (pin "2") (pinfunction "2_2") (pintype "passive"))
      (node (ref "C57") (pin "2") (pinfunction "2_2") (pintype "passive"))
      (node (ref "C58") (pin "2") (pinfunction "2_2") (pintype "passive"))
      (node (ref "C59") (pin "2") (pinfunction "2_2") (pintype "passive"))
      (node (ref "C6") (pin "2") (pinfunction "2_2") (pintype "passive"))
      (node (ref "C60") (pin "2") (pinfunction "2_2") (pintype "passive"))
      (node (ref "C61") (pin "2") (pinfunction "2_2") (pintype "passive"))
      (node (ref "C62") (pin "2") (pinfunction "2_2") (pintype "passive"))
      (node (ref "C63") (pin "2") (pinfunction "2_2") (pintype "passive"))
      (node (ref "C64") (pin "1") (pinfunction "1_1") (pintype "passive"))
      (node (ref "C65") (pin "1") (pinfunction "1_1") (pintype "passive"))
      (node (ref "C67") (pin "1") (pinfunction "1_1") (pintype "passive"))
      (node (ref "C68") (pin "1") (pinfunction "1_1") (pintype "passive"))
      (node (ref "C70") (pin "2") (pinfunction "2_2") (pintype "passive"))
      (node (ref "C71") (pin "2") (pinfunction "2_2") (pintype "passive"))
      (node (ref "C72") (pin "2") (pinfunction "2_2") (pintype "passive"))
      (node (ref "C73") (pin "2") (pinfunction "2_2") (pintype "passive"))
      (node (ref "C74") (pin "2") (pinfunction "2_2") (pintype "passive"))
      (node (ref "C75") (pin "2") (pinfunction "2_2") (pintype "passive"))
      (node (ref "C76") (pin "2") (pinfunction "2_2") (pintype "passive"))
      (node (ref "C77") (pin "2") (pinfunction "2_2") (pintype "passive"))
      (node (ref "C78") (pin "2") (pinfunction "2_2") (pintype "passive"))
      (node (ref "C79") (pin "2") (pinfunction "2_2") (pintype "passive"))
      (node (ref "C8") (pin "2") (pinfunction "2_2") (pintype "passive"))
      (node (ref "C80") (pin "2") (pinfunction "2_2") (pintype "passive"))
      (node (ref "C81") (pin "2") (pinfunction "2_2") (pintype "passive"))
      (node (ref "C82") (pin "2") (pinfunction "2_2") (pintype "passive"))
      (node (ref "C83") (pin "2") (pinfunction "2_2") (pintype "passive"))
      (node (ref "C84") (pin "2") (pinfunction "2_2") (pintype "passive"))
      (node (ref "C85") (pin "2") (pinfunction "2_2") (pintype "passive"))
      (node (ref "C86") (pin "2") (pinfunction "2_2") (pintype "passive"))
      (node (ref "C87") (pin "2") (pinfunction "2_2") (pintype "passive"))
      (node (ref "C88") (pin "2") (pinfunction "2_2") (pintype "passive"))
      (node (ref "D4") (pin "A") (pinfunction "A_A") (pintype "passive"))
      (node (ref "D5") (pin "A") (pinfunction "A_A") (pintype "passive"))
      (node (ref "D6") (pin "A") (pinfunction "A_A") (pintype "passive"))
      (node (ref "IC1") (pin "1") (pinfunction "CLK_1") (pintype "bidirectional"))
      (node (ref "IC1") (pin "10") (pinfunction "SPI_MODE_10") (pintype "bidirectional"))
      (node (ref "IC1") (pin "11") (pinfunction "GND_11") (pintype "bidirectional"))
      (node (ref "IC1") (pin "12") (pinfunction "GND_12") (pintype "bidirectional"))
      (node (ref "IC1") (pin "24") (pinfunction "GNDA_24") (pintype "bidirectional"))
      (node (ref "IC1") (pin "35") (pinfunction "GND_35") (pintype "bidirectional"))
      (node (ref "IC1") (pin "36") (pinfunction "TST_MODE_36") (pintype "bidirectional"))
      (node (ref "IC1") (pin "TP") (pinfunction "GND_TP") (pintype "bidirectional"))
      (node (ref "IC10") (pin "3") (pinfunction "GND_3") (pintype "power_in"))
      (node (ref "IC11") (pin "3") (pinfunction "GND_3") (pintype "power_in"))
      (node (ref "IC12") (pin "1") (pinfunction "CLK_1") (pintype "bidirectional"))
      (node (ref "IC12") (pin "10") (pinfunction "SPI_MODE_10") (pintype "bidirectional"))
      (node (ref "IC12") (pin "11") (pinfunction "GND_11") (pintype "bidirectional"))
      (node (ref "IC12") (pin "12") (pinfunction "GND_12") (pintype "bidirectional"))
      (node (ref "IC12") (pin "24") (pinfunction "GNDA_24") (pintype "bidirectional"))
      (node (ref "IC12") (pin "35") (pinfunction "GND_35") (pintype "bidirectional"))
      (node (ref "IC12") (pin "36") (pinfunction "TST_MODE_36") (pintype "bidirectional"))
      (node (ref "IC12") (pin "TP") (pinfunction "GND_TP") (pintype "bidirectional"))
      (node (ref "IC13") (pin "3") (pinfunction "GND_3") (pintype "power_in"))
      (node (ref "IC14") (pin "3") (pinfunction "GND_3") (pintype "power_in"))
      (node (ref "IC15") (pin "1") (pinfunction "CLK_1") (pintype "bidirectional"))
      (node (ref "IC15") (pin "10") (pinfunction "SPI_MODE_10") (pintype "bidirectional"))
      (node (ref "IC15") (pin "11") (pinfunction "GND_11") (pintype "bidirectional"))
      (node (ref "IC15") (pin "12") (pinfunction "GND_12") (pintype "bidirectional"))
      (node (ref "IC15") (pin "24") (pinfunction "GNDA_24") (pintype "bidirectional"))
      (node (ref "IC15") (pin "35") (pinfunction "GND_35") (pintype "bidirectional"))
      (node (ref "IC15") (pin "36") (pinfunction "TST_MODE_36") (pintype "bidirectional"))
      (node (ref "IC15") (pin "TP") (pinfunction "GND_TP") (pintype "bidirectional"))
      (node (ref "IC16") (pin "3") (pinfunction "GND_3") (pintype "power_in"))
      (node (ref "IC17") (pin "3") (pinfunction "GND_3") (pintype "power_in"))
      (node (ref "IC18") (pin "3") (pinfunction "GND_3") (pintype "power_in"))
      (node (ref "IC19") (pin "3") (pinfunction "GND_3") (pintype "power_in"))
      (node (ref "IC2") (pin "1") (pinfunction "CLK_1") (pintype "bidirectional"))
      (node (ref "IC2") (pin "10") (pinfunction "SPI_MODE_10") (pintype "bidirectional"))
      (node (ref "IC2") (pin "11") (pinfunction "GND_11") (pintype "bidirectional"))
      (node (ref "IC2") (pin "12") (pinfunction "GND_12") (pintype "bidirectional"))
      (node (ref "IC2") (pin "24") (pinfunction "GNDA_24") (pintype "bidirectional"))
      (node (ref "IC2") (pin "35") (pinfunction "GND_35") (pintype "bidirectional"))
      (node (ref "IC2") (pin "36") (pinfunction "TST_MODE_36") (pintype "bidirectional"))
      (node (ref "IC2") (pin "TP") (pinfunction "GND_TP") (pintype "bidirectional"))
      (node (ref "IC3") (pin "3") (pinfunction "GND_3") (pintype "power_in"))
      (node (ref "IC4") (pin "3") (pinfunction "GND_3") (pintype "power_in"))
      (node (ref "IC5") (pin "1") (pinfunction "CLK_1") (pintype "bidirectional"))
      (node (ref "IC5") (pin "10") (pinfunction "SPI_MODE_10") (pintype "bidirectional"))
      (node (ref "IC5") (pin "11") (pinfunction "GND_11") (pintype "bidirectional"))
      (node (ref "IC5") (pin "12") (pinfunction "GND_12") (pintype "bidirectional"))
      (node (ref "IC5") (pin "24") (pinfunction "GNDA_24") (pintype "bidirectional"))
      (node (ref "IC5") (pin "35") (pinfunction "GND_35") (pintype "bidirectional"))
      (node (ref "IC5") (pin "36") (pinfunction "TST_MODE_36") (pintype "bidirectional"))
      (node (ref "IC5") (pin "TP") (pinfunction "GND_TP") (pintype "bidirectional"))
      (node (ref "IC6") (pin "3") (pinfunction "GND_3") (pintype "power_in"))
      (node (ref "IC7") (pin "3") (pinfunction "GND_3") (pintype "power_in"))
      (node (ref "IC8") (pin "3") (pinfunction "GND_3") (pintype "power_in"))
      (node (ref "IC9") (pin "3") (pinfunction "GND_3") (pintype "power_in"))
      (node (ref "LED4") (pin "C") (pinfunction "C_C") (pintype "passive"))
      (node (ref "P8") (pin "1") (pinfunction "1_1") (pintype "passive"))
      (node (ref "P8") (pin "2") (pinfunction "2_2") (pintype "passive"))
      (node (ref "P9") (pin "1") (pinfunction "1_1") (pintype "passive"))
      (node (ref "P9") (pin "2") (pinfunction "2_2") (pintype "passive"))
      (node (ref "P9") (pin "43") (pinfunction "43_43") (pintype "passive"))
      (node (ref "P9") (pin "44") (pinfunction "44_44") (pintype "passive"))
      (node (ref "P9") (pin "45") (pinfunction "45_45") (pintype "passive"))
      (node (ref "P9") (pin "46") (pinfunction "46_46") (pintype "passive"))
      (node (ref "Q1") (pin "1") (pinfunction "S_1") (pintype "passive"))
      (node (ref "Q1") (pin "2") (pinfunction "S_2") (pintype "passive"))
      (node (ref "Q1") (pin "3") (pinfunction "S_3") (pintype "passive"))
      (node (ref "Q2") (pin "1") (pinfunction "S_1") (pintype "passive"))
      (node (ref "Q2") (pin "2") (pinfunction "S_2") (pintype "passive"))
      (node (ref "Q2") (pin "3") (pinfunction "S_3") (pintype "passive"))
      (node (ref "Q3") (pin "1") (pinfunction "S_1") (pintype "passive"))
      (node (ref "Q3") (pin "2") (pinfunction "S_2") (pintype "passive"))
      (node (ref "Q3") (pin "3") (pinfunction "S_3") (pintype "passive"))
      (node (ref "Q4") (pin "2") (pinfunction "E_2") (pintype "passive"))
      (node (ref "Q5") (pin "2") (pinfunction "E_2") (pintype "passive"))
      (node (ref "Q6") (pin "2") (pinfunction "E_2") (pintype "passive"))
      (node (ref "Q7") (pin "2") (pinfunction "E_2") (pintype "passive"))
      (node (ref "R1") (pin "1") (pinfunction "1_1") (pintype "passive"))
      (node (ref "R10") (pin "1") (pinfunction "1_1") (pintype "passive"))
      (node (ref "R2") (pin "1") (pinfunction "1_1") (pintype "passive"))
      (node (ref "R22") (pin "2") (pinfunction "2_2") (pintype "passive"))
      (node (ref "R26") (pin "2") (pinfunction "2_2") (pintype "passive"))
      (node (ref "R29") (pin "1") (pinfunction "1_1") (pintype "passive"))
      (node (ref "R3") (pin "1") (pinfunction "1_1") (pintype "passive"))
      (node (ref "R30") (pin "1") (pinfunction "1_1") (pintype "passive"))
      (node (ref "R32") (pin "1") (pinfunction "1_1") (pintype "passive"))
      (node (ref "R33") (pin "1") (pinfunction "1_1") (pintype "passive"))
      (node (ref "R34") (pin "1") (pinfunction "1_1") (pintype "passive"))
      (node (ref "R4") (pin "1") (pinfunction "1_1") (pintype "passive"))
      (node (ref "R43") (pin "2") (pinfunction "2_2") (pintype "passive"))
      (node (ref "R44") (pin "2") (pinfunction "2_2") (pintype "passive"))
      (node (ref "R46") (pin "1") (pinfunction "1_1") (pintype "passive"))
      (node (ref "R47") (pin "1") (pinfunction "1_1") (pintype "passive"))
      (node (ref "R48") (pin "1") (pinfunction "1_1") (pintype "passive"))
      (node (ref "R5") (pin "1") (pinfunction "1_1") (pintype "passive"))
      (node (ref "R7") (pin "1") (pinfunction "1_1") (pintype "passive"))
      (node (ref "R8") (pin "1") (pinfunction "1_1") (pintype "passive"))
      (node (ref "R9") (pin "1") (pinfunction "1_1") (pintype "passive"))
      (node (ref "U1") (pin "13") (pinfunction "~{OE}_13") (pintype "input"))
      (node (ref "U1") (pin "8") (pinfunction "GND_8") (pintype "passive"))
      (node (ref "U10") (pin "6") (pinfunction "GND_6") (pintype "power_in"))
      (node (ref "U10") (pin "EP") (pinfunction "EP_EP") (pintype "power_in"))
      (node (ref "U11") (pin "14") (pinfunction "VSS_14") (pintype "passive"))
      (node (ref "U18") (pin "1") (pinfunction "A0_1") (pintype "input"))
      (node (ref "U18") (pin "2") (pinfunction "A1_2") (pintype "input"))
      (node (ref "U18") (pin "4") (pinfunction "GND_4") (pintype "power_in"))
      (node (ref "U19") (pin "8") (pinfunction "VSS_8") (pintype "power_in"))
      (node (ref "U2") (pin "13") (pinfunction "~{OE}_13") (pintype "input"))
      (node (ref "U2") (pin "8") (pinfunction "GND_8") (pintype "passive"))
      (node (ref "U3") (pin "13") (pinfunction "~{OE}_13") (pintype "input"))
      (node (ref "U3") (pin "8") (pinfunction "GND_8") (pintype "passive"))
      (node (ref "U4") (pin "13") (pinfunction "~{OE}_13") (pintype "input"))
      (node (ref "U4") (pin "8") (pinfunction "GND_8") (pintype "passive"))
      (node (ref "U5") (pin "13") (pinfunction "~{OE}_13") (pintype "input"))
      (node (ref "U5") (pin "8") (pinfunction "GND_8") (pintype "passive"))
      (node (ref "U6") (pin "6") (pinfunction "GND_6") (pintype "power_in"))
      (node (ref "U6") (pin "EP") (pinfunction "EP_EP") (pintype "power_in"))
      (node (ref "X1") (pin "2") (pinfunction "S_2") (pintype "passive"))
      (node (ref "X10") (pin "2") (pinfunction "S_2") (pintype "passive"))
      (node (ref "X11") (pin "1") (pinfunction "S_1") (pintype "passive"))
      (node (ref "X12") (pin "2") (pinfunction "S_2") (pintype "passive"))
      (node (ref "X13") (pin "2") (pinfunction "S_2") (pintype "passive"))
      (node (ref "X19") (pin "2") (pinfunction "S_2") (pintype "passive"))
      (node (ref "X2") (pin "1") (pinfunction "1_1") (pintype "passive"))
      (node (ref "X2") (pin "2") (pinfunction "1_2") (pintype "passive"))
      (node (ref "X22") (pin "2") (pinfunction "S_2") (pintype "passive"))
      (node (ref "X23") (pin "3") (pinfunction "S_3") (pintype "passive"))
      (node (ref "X7") (pin "1") (pinfunction "S_1") (pintype "passive"))
      (node (ref "X8") (pin "1") (pinfunction "S_1") (pintype "passive"))
    )
    (net (code "68") (name "Net-(C51-Pad2)") (class "Default")
      (node (ref "C51") (pin "2") (pinfunction "2_2") (pintype "passive"))
      (node (ref "R26") (pin "1") (pinfunction "1_1") (pintype "passive"))
    )
    (net (code "69") (name "Net-(C56-Pad2)") (class "Default")
      (node (ref "C56") (pin "2") (pinfunction "2_2") (pintype "passive"))
      (node (ref "R44") (pin "1") (pinfunction "1_1") (pintype "passive"))
    )
    (net (code "70") (name "Net-(C75-Pad1)") (class "Default")
      (node (ref "C75") (pin "1") (pinfunction "1_1") (pintype "passive"))
      (node (ref "R31") (pin "1") (pinfunction "1_1") (pintype "passive"))
      (node (ref "R50") (pin "2") (pinfunction "2_2") (pintype "passive"))
    )
    (net (code "71") (name "Net-(C76-Pad1)") (class "Default")
      (node (ref "C76") (pin "1") (pinfunction "1_1") (pintype "passive"))
      (node (ref "R37") (pin "1") (pinfunction "1_1") (pintype "passive"))
      (node (ref "R6") (pin "2") (pinfunction "2_2") (pintype "passive"))
    )
    (net (code "72") (name "Net-(C77-Pad1)") (class "Default")
      (node (ref "C77") (pin "1") (pinfunction "1_1") (pintype "passive"))
      (node (ref "R41") (pin "1") (pinfunction "1_1") (pintype "passive"))
      (node (ref "R49") (pin "2") (pinfunction "2_2") (pintype "passive"))
    )
    (net (code "73") (name "Net-(C78-Pad1)") (class "Default")
      (node (ref "C78") (pin "1") (pinfunction "1_1") (pintype "passive"))
      (node (ref "R27") (pin "2") (pinfunction "2_2") (pintype "passive"))
      (node (ref "R58") (pin "1") (pinfunction "1_1") (pintype "passive"))
    )
    (net (code "74") (name "Net-(C79-Pad1)") (class "Default")
      (node (ref "C79") (pin "1") (pinfunction "1_1") (pintype "passive"))
      (node (ref "R35") (pin "2") (pinfunction "2_2") (pintype "passive"))
      (node (ref "R60") (pin "1") (pinfunction "1_1") (pintype "passive"))
    )
    (net (code "75") (name "Net-(FAN0-PadA)") (class "Default")
      (node (ref "FAN0") (pin "A") (pinfunction "A_A") (pintype "passive"))
      (node (ref "R25") (pin "1") (pinfunction "1_1") (pintype "passive"))
    )
    (net (code "76") (name "Net-(IC1-5VOUT)") (class "Default")
      (node (ref "C21") (pin "2") (pinfunction "2_2") (pintype "passive"))
      (node (ref "IC1") (pin "25") (pinfunction "5VOUT_25") (pintype "bidirectional"))
      (node (ref "R53") (pin "1") (pinfunction "1_1") (pintype "passive"))
    )
    (net (code "77") (name "Net-(IC1-AIN_IREF)") (class "Default")
      (node (ref "C12") (pin "1") (pinfunction "1_1") (pintype "passive"))
      (node (ref "IC1") (pin "23") (pinfunction "AIN_IREF_23") (pintype "bidirectional"))
      (node (ref "R49") (pin "1") (pinfunction "1_1") (pintype "passive"))
    )
    (net (code "78") (name "Net-(IC1-BRA)") (class "Default")
      (node (ref "IC1") (pin "33") (pinfunction "BRA_33") (pintype "bidirectional"))
      (node (ref "R2") (pin "2") (pinfunction "2_2") (pintype "passive"))
    )
    (net (code "79") (name "Net-(IC1-BRB)") (class "Default")
      (node (ref "IC1") (pin "14") (pinfunction "BRB_14") (pintype "bidirectional"))
      (node (ref "R1") (pin "2") (pinfunction "2_2") (pintype "passive"))
    )
    (net (code "80") (name "Net-(IC1-CPI)") (class "Default")
      (node (ref "C1") (pin "1") (pinfunction "1_1") (pintype "passive"))
      (node (ref "IC1") (pin "28") (pinfunction "CPI_28") (pintype "bidirectional"))
    )
    (net (code "81") (name "Net-(IC1-CPO)") (class "Default")
      (node (ref "C1") (pin "2") (pinfunction "2_2") (pintype "passive"))
      (node (ref "IC1") (pin "27") (pinfunction "CPO_27") (pintype "bidirectional"))
    )
    (net (code "82") (name "Net-(IC1-ENCA_DCIN_CFG5)") (class "Default")
      (node (ref "IC1") (pin "19") (pinfunction "ENCA_DCIN_CFG5_19") (pintype "bidirectional"))
      (node (ref "U1") (pin "1") (pinfunction "QB_1") (pintype "output"))
    )
    (net (code "83") (name "Net-(IC1-ENCB_DCEN_CFG4)") (class "Default")
      (node (ref "IC1") (pin "18") (pinfunction "ENCB_DCEN_CFG4_18") (pintype "bidirectional"))
      (node (ref "U1") (pin "2") (pinfunction "QC_2") (pintype "output"))
    )
    (net (code "84") (name "Net-(IC1-OA1)") (class "Default")
      (node (ref "IC1") (pin "34") (pinfunction "OA1_34") (pintype "bidirectional"))
      (node (ref "X14") (pin "2") (pinfunction "S_2") (pintype "passive"))
    )
    (net (code "85") (name "Net-(IC1-OA2)") (class "Default")
      (node (ref "IC1") (pin "32") (pinfunction "OA2_32") (pintype "bidirectional"))
      (node (ref "X14") (pin "1") (pinfunction "S_1") (pintype "passive"))
    )
    (net (code "86") (name "Net-(IC1-OB1)") (class "Default")
      (node (ref "IC1") (pin "13") (pinfunction "OB1_13") (pintype "bidirectional"))
      (node (ref "X14") (pin "3") (pinfunction "S_3") (pintype "passive"))
    )
    (net (code "87") (name "Net-(IC1-OB2)") (class "Default")
      (node (ref "IC1") (pin "15") (pinfunction "OB2_15") (pintype "bidirectional"))
      (node (ref "X14") (pin "4") (pinfunction "S_4") (pintype "passive"))
    )
    (net (code "88") (name "Net-(IC1-SCK_CFG2)") (class "Default")
      (node (ref "IC1") (pin "3") (pinfunction "SCK_CFG2_3") (pintype "bidirectional"))
      (node (ref "IC3") (pin "4") (pinfunction "O_4") (pintype "output"))
    )
    (net (code "89") (name "Net-(IC1-SDI_NAI_CFG1)") (class "Default")
      (node (ref "IC1") (pin "4") (pinfunction "SDI_NAI_CFG1_4") (pintype "bidirectional"))
      (node (ref "IC4") (pin "4") (pinfunction "O_4") (pintype "output"))
    )
    (net (code "90") (name "Net-(IC1-SDO_NAO_CFG0)") (class "Default")
      (node (ref "IC1") (pin "5") (pinfunction "SDO_NAO_CFG0_5") (pintype "bidirectional"))
      (node (ref "U1") (pin "3") (pinfunction "QD_3") (pintype "output"))
    )
    (net (code "91") (name "Net-(IC1-VCC)") (class "Default")
      (node (ref "C71") (pin "1") (pinfunction "1_1") (pintype "passive"))
      (node (ref "IC1") (pin "26") (pinfunction "VCC_26") (pintype "bidirectional"))
      (node (ref "R53") (pin "2") (pinfunction "2_2") (pintype "passive"))
    )
    (net (code "92") (name "Net-(IC1-VCP)") (class "Default")
      (node (ref "C22") (pin "1") (pinfunction "1_1") (pintype "passive"))
      (node (ref "IC1") (pin "29") (pinfunction "VCP_29") (pintype "bidirectional"))
    )
    (net (code "93") (name "Net-(IC2-5VOUT)") (class "Default")
      (node (ref "C33") (pin "2") (pinfunction "2_2") (pintype "passive"))
      (node (ref "IC2") (pin "25") (pinfunction "5VOUT_25") (pintype "bidirectional"))
      (node (ref "R59") (pin "1") (pinfunction "1_1") (pintype "passive"))
    )
    (net (code "94") (name "Net-(IC2-AIN_IREF)") (class "Default")
      (node (ref "C18") (pin "1") (pinfunction "1_1") (pintype "passive"))
      (node (ref "IC2") (pin "23") (pinfunction "AIN_IREF_23") (pintype "bidirectional"))
      (node (ref "R6") (pin "1") (pinfunction "1_1") (pintype "passive"))
    )
    (net (code "95") (name "Net-(IC2-BRA)") (class "Default")
      (node (ref "IC2") (pin "33") (pinfunction "BRA_33") (pintype "bidirectional"))
      (node (ref "R4") (pin "2") (pinfunction "2_2") (pintype "passive"))
    )
    (net (code "96") (name "Net-(IC2-BRB)") (class "Default")
      (node (ref "IC2") (pin "14") (pinfunction "BRB_14") (pintype "bidirectional"))
      (node (ref "R3") (pin "2") (pinfunction "2_2") (pintype "passive"))
    )
    (net (code "97") (name "Net-(IC2-CPI)") (class "Default")
      (node (ref "C3") (pin "1") (pinfunction "1_1") (pintype "passive"))
      (node (ref "IC2") (pin "28") (pinfunction "CPI_28") (pintype "bidirectional"))
    )
    (net (code "98") (name "Net-(IC2-CPO)") (class "Default")
      (node (ref "C3") (pin "2") (pinfunction "2_2") (pintype "passive"))
      (node (ref "IC2") (pin "27") (pinfunction "CPO_27") (pintype "bidirectional"))
    )
    (net (code "99") (name "Net-(IC2-ENCA_DCIN_CFG5)") (class "Default")
      (node (ref "IC2") (pin "19") (pinfunction "ENCA_DCIN_CFG5_19") (pintype "bidirectional"))
      (node (ref "U2") (pin "1") (pinfunction "QB_1") (pintype "output"))
    )
    (net (code "100") (name "Net-(IC2-ENCB_DCEN_CFG4)") (class "Default")
      (node (ref "IC2") (pin "18") (pinfunction "ENCB_DCEN_CFG4_18") (pintype "bidirectional"))
      (node (ref "U2") (pin "2") (pinfunction "QC_2") (pintype "output"))
    )
    (net (code "101") (name "Net-(IC2-OA1)") (class "Default")
      (node (ref "IC2") (pin "34") (pinfunction "OA1_34") (pintype "bidirectional"))
      (node (ref "X15") (pin "2") (pinfunction "S_2") (pintype "passive"))
    )
    (net (code "102") (name "Net-(IC2-OA2)") (class "Default")
      (node (ref "IC2") (pin "32") (pinfunction "OA2_32") (pintype "bidirectional"))
      (node (ref "X15") (pin "1") (pinfunction "S_1") (pintype "passive"))
    )
    (net (code "103") (name "Net-(IC2-OB1)") (class "Default")
      (node (ref "IC2") (pin "13") (pinfunction "OB1_13") (pintype "bidirectional"))
      (node (ref "X15") (pin "3") (pinfunction "S_3") (pintype "passive"))
    )
    (net (code "104") (name "Net-(IC2-OB2)") (class "Default")
      (node (ref "IC2") (pin "15") (pinfunction "OB2_15") (pintype "bidirectional"))
      (node (ref "X15") (pin "4") (pinfunction "S_4") (pintype "passive"))
    )
    (net (code "105") (name "Net-(IC2-SCK_CFG2)") (class "Default")
      (node (ref "IC2") (pin "3") (pinfunction "SCK_CFG2_3") (pintype "bidirectional"))
      (node (ref "IC8") (pin "4") (pinfunction "O_4") (pintype "output"))
    )
    (net (code "106") (name "Net-(IC2-SDI_NAI_CFG1)") (class "Default")
      (node (ref "IC2") (pin "4") (pinfunction "SDI_NAI_CFG1_4") (pintype "bidirectional"))
      (node (ref "IC9") (pin "4") (pinfunction "O_4") (pintype "output"))
    )
    (net (code "107") (name "Net-(IC2-SDO_NAO_CFG0)") (class "Default")
      (node (ref "IC2") (pin "5") (pinfunction "SDO_NAO_CFG0_5") (pintype "bidirectional"))
      (node (ref "U2") (pin "3") (pinfunction "QD_3") (pintype "output"))
    )
    (net (code "108") (name "Net-(IC2-VCC)") (class "Default")
      (node (ref "C72") (pin "1") (pinfunction "1_1") (pintype "passive"))
      (node (ref "IC2") (pin "26") (pinfunction "VCC_26") (pintype "bidirectional"))
      (node (ref "R59") (pin "2") (pinfunction "2_2") (pintype "passive"))
    )
    (net (code "109") (name "Net-(IC2-VCP)") (class "Default")
      (node (ref "C35") (pin "1") (pinfunction "1_1") (pintype "passive"))
      (node (ref "IC2") (pin "29") (pinfunction "VCP_29") (pintype "bidirectional"))
    )
    (net (code "110") (name "Net-(IC3A-I)") (class "Default")
      (node (ref "IC3") (pin "2") (pinfunction "I_2") (pintype "input"))
      (node (ref "U1") (pin "4") (pinfunction "QE_4") (pintype "output"))
    )
    (net (code "111") (name "Net-(IC3A-OE)") (class "Default")
      (node (ref "IC3") (pin "1") (pinfunction "OE_1") (pintype "input"))
      (node (ref "U1") (pin "5") (pinfunction "QF_5") (pintype "output"))
    )
    (net (code "112") (name "Net-(IC4A-I)") (class "Default")
      (node (ref "IC4") (pin "2") (pinfunction "I_2") (pintype "input"))
      (node (ref "U1") (pin "6") (pinfunction "QG_6") (pintype "output"))
    )
    (net (code "113") (name "Net-(IC4A-OE)") (class "Default")
      (node (ref "IC4") (pin "1") (pinfunction "OE_1") (pintype "input"))
      (node (ref "U1") (pin "7") (pinfunction "QH_7") (pintype "output"))
    )
    (net (code "114") (name "Net-(IC5-5VOUT)") (class "Default")
      (node (ref "C37") (pin "2") (pinfunction "2_2") (pintype "passive"))
      (node (ref "IC5") (pin "25") (pinfunction "5VOUT_25") (pintype "bidirectional"))
      (node (ref "R70") (pin "1") (pinfunction "1_1") (pintype "passive"))
    )
    (net (code "115") (name "Net-(IC5-AIN_IREF)") (class "Default")
      (node (ref "C25") (pin "1") (pinfunction "1_1") (pintype "passive"))
      (node (ref "IC5") (pin "23") (pinfunction "AIN_IREF_23") (pintype "bidirectional"))
      (node (ref "R27") (pin "1") (pinfunction "1_1") (pintype "passive"))
    )
    (net (code "116") (name "Net-(IC5-BRA)") (class "Default")
      (node (ref "IC5") (pin "33") (pinfunction "BRA_33") (pintype "bidirectional"))
      (node (ref "R8") (pin "2") (pinfunction "2_2") (pintype "passive"))
    )
    (net (code "117") (name "Net-(IC5-BRB)") (class "Default")
      (node (ref "IC5") (pin "14") (pinfunction "BRB_14") (pintype "bidirectional"))
      (node (ref "R7") (pin "2") (pinfunction "2_2") (pintype "passive"))
    )
    (net (code "118") (name "Net-(IC5-CPI)") (class "Default")
      (node (ref "C7") (pin "1") (pinfunction "1_1") (pintype "passive"))
      (node (ref "IC5") (pin "28") (pinfunction "CPI_28") (pintype "bidirectional"))
    )
    (net (code "119") (name "Net-(IC5-CPO)") (class "Default")
      (node (ref "C7") (pin "2") (pinfunction "2_2") (pintype "passive"))
      (node (ref "IC5") (pin "27") (pinfunction "CPO_27") (pintype "bidirectional"))
    )
    (net (code "120") (name "Net-(IC5-ENCA_DCIN_CFG5)") (class "Default")
      (node (ref "IC5") (pin "19") (pinfunction "ENCA_DCIN_CFG5_19") (pintype "bidirectional"))
      (node (ref "U3") (pin "1") (pinfunction "QB_1") (pintype "output"))
    )
    (net (code "121") (name "Net-(IC5-ENCB_DCEN_CFG4)") (class "Default")
      (node (ref "IC5") (pin "18") (pinfunction "ENCB_DCEN_CFG4_18") (pintype "bidirectional"))
      (node (ref "U3") (pin "2") (pinfunction "QC_2") (pintype "output"))
    )
    (net (code "122") (name "Net-(IC5-OA1)") (class "Default")
      (node (ref "IC5") (pin "34") (pinfunction "OA1_34") (pintype "bidirectional"))
      (node (ref "X16") (pin "2") (pinfunction "S_2") (pintype "passive"))
    )
    (net (code "123") (name "Net-(IC5-OA2)") (class "Default")
      (node (ref "IC5") (pin "32") (pinfunction "OA2_32") (pintype "bidirectional"))
      (node (ref "X16") (pin "1") (pinfunction "S_1") (pintype "passive"))
    )
    (net (code "124") (name "Net-(IC5-OB1)") (class "Default")
      (node (ref "IC5") (pin "13") (pinfunction "OB1_13") (pintype "bidirectional"))
      (node (ref "X16") (pin "3") (pinfunction "S_3") (pintype "passive"))
    )
    (net (code "125") (name "Net-(IC5-OB2)") (class "Default")
      (node (ref "IC5") (pin "15") (pinfunction "OB2_15") (pintype "bidirectional"))
      (node (ref "X16") (pin "4") (pinfunction "S_4") (pintype "passive"))
    )
    (net (code "126") (name "Net-(IC5-SDO_NAO_CFG0)") (class "Default")
      (node (ref "IC5") (pin "5") (pinfunction "SDO_NAO_CFG0_5") (pintype "bidirectional"))
      (node (ref "U3") (pin "3") (pinfunction "QD_3") (pintype "output"))
    )
    (net (code "127") (name "Net-(IC5-VCC)") (class "Default")
      (node (ref "C73") (pin "1") (pinfunction "1_1") (pintype "passive"))
      (node (ref "IC5") (pin "26") (pinfunction "VCC_26") (pintype "bidirectional"))
      (node (ref "R70") (pin "2") (pinfunction "2_2") (pintype "passive"))
    )
    (net (code "128") (name "Net-(IC5-VCP)") (class "Default")
      (node (ref "C38") (pin "1") (pinfunction "1_1") (pintype "passive"))
      (node (ref "IC5") (pin "29") (pinfunction "VCP_29") (pintype "bidirectional"))
    )
    (net (code "129") (name "Net-(IC8A-I)") (class "Default")
      (node (ref "IC8") (pin "2") (pinfunction "I_2") (pintype "input"))
      (node (ref "U2") (pin "4") (pinfunction "QE_4") (pintype "output"))
    )
    (net (code "130") (name "Net-(IC8A-OE)") (class "Default")
      (node (ref "IC8") (pin "1") (pinfunction "OE_1") (pintype "input"))
      (node (ref "U2") (pin "5") (pinfunction "QF_5") (pintype "output"))
    )
    (net (code "131") (name "Net-(IC9A-I)") (class "Default")
      (node (ref "IC9") (pin "2") (pinfunction "I_2") (pintype "input"))
      (node (ref "U2") (pin "6") (pinfunction "QG_6") (pintype "output"))
    )
    (net (code "132") (name "Net-(IC9A-OE)") (class "Default")
      (node (ref "IC9") (pin "1") (pinfunction "OE_1") (pintype "input"))
      (node (ref "U2") (pin "7") (pinfunction "QH_7") (pintype "output"))
    )
    (net (code "133") (name "Net-(IC10A-I)") (class "Default")
      (node (ref "IC10") (pin "2") (pinfunction "I_2") (pintype "input"))
      (node (ref "U3") (pin "4") (pinfunction "QE_4") (pintype "output"))
    )
    (net (code "134") (name "Net-(IC10A-O)") (class "Default")
      (node (ref "IC10") (pin "4") (pinfunction "O_4") (pintype "output"))
      (node (ref "IC5") (pin "3") (pinfunction "SCK_CFG2_3") (pintype "bidirectional"))
    )
    (net (code "135") (name "Net-(IC10A-OE)") (class "Default")
      (node (ref "IC10") (pin "1") (pinfunction "OE_1") (pintype "input"))
      (node (ref "U3") (pin "5") (pinfunction "QF_5") (pintype "output"))
    )
    (net (code "136") (name "Net-(IC11A-I)") (class "Default")
      (node (ref "IC11") (pin "2") (pinfunction "I_2") (pintype "input"))
      (node (ref "U3") (pin "6") (pinfunction "QG_6") (pintype "output"))
    )
    (net (code "137") (name "Net-(IC11A-O)") (class "Default")
      (node (ref "IC11") (pin "4") (pinfunction "O_4") (pintype "output"))
      (node (ref "IC5") (pin "4") (pinfunction "SDI_NAI_CFG1_4") (pintype "bidirectional"))
    )
    (net (code "138") (name "Net-(IC11A-OE)") (class "Default")
      (node (ref "IC11") (pin "1") (pinfunction "OE_1") (pintype "input"))
      (node (ref "U3") (pin "7") (pinfunction "QH_7") (pintype "output"))
    )
    (net (code "139") (name "Net-(IC12-5VOUT)") (class "Default")
      (node (ref "C65") (pin "2") (pinfunction "2_2") (pintype "passive"))
      (node (ref "IC12") (pin "25") (pinfunction "5VOUT_25") (pintype "bidirectional"))
      (node (ref "R71") (pin "1") (pinfunction "1_1") (pintype "passive"))
    )
    (net (code "140") (name "Net-(IC12-AIN_IREF)") (class "Default")
      (node (ref "C62") (pin "1") (pinfunction "1_1") (pintype "passive"))
      (node (ref "IC12") (pin "23") (pinfunction "AIN_IREF_23") (pintype "bidirectional"))
      (node (ref "R35") (pin "1") (pinfunction "1_1") (pintype "passive"))
    )
    (net (code "141") (name "Net-(IC12-BRA)") (class "Default")
      (node (ref "IC12") (pin "33") (pinfunction "BRA_33") (pintype "bidirectional"))
      (node (ref "R30") (pin "2") (pinfunction "2_2") (pintype "passive"))
    )
    (net (code "142") (name "Net-(IC12-BRB)") (class "Default")
      (node (ref "IC12") (pin "14") (pinfunction "BRB_14") (pintype "bidirectional"))
      (node (ref "R29") (pin "2") (pinfunction "2_2") (pintype "passive"))
    )
    (net (code "143") (name "Net-(IC12-CPI)") (class "Default")
      (node (ref "C39") (pin "1") (pinfunction "1_1") (pintype "passive"))
      (node (ref "IC12") (pin "28") (pinfunction "CPI_28") (pintype "bidirectional"))
    )
    (net (code "144") (name "Net-(IC12-CPO)") (class "Default")
      (node (ref "C39") (pin "2") (pinfunction "2_2") (pintype "passive"))
      (node (ref "IC12") (pin "27") (pinfunction "CPO_27") (pintype "bidirectional"))
    )
    (net (code "145") (name "Net-(IC12-ENCA_DCIN_CFG5)") (class "Default")
      (node (ref "IC12") (pin "19") (pinfunction "ENCA_DCIN_CFG5_19") (pintype "bidirectional"))
      (node (ref "U4") (pin "1") (pinfunction "QB_1") (pintype "output"))
    )
    (net (code "146") (name "Net-(IC12-ENCB_DCEN_CFG4)") (class "Default")
      (node (ref "IC12") (pin "18") (pinfunction "ENCB_DCEN_CFG4_18") (pintype "bidirectional"))
      (node (ref "U4") (pin "2") (pinfunction "QC_2") (pintype "output"))
    )
    (net (code "147") (name "Net-(IC12-OA1)") (class "Default")
      (node (ref "IC12") (pin "34") (pinfunction "OA1_34") (pintype "bidirectional"))
      (node (ref "X17") (pin "2") (pinfunction "S_2") (pintype "passive"))
    )
    (net (code "148") (name "Net-(IC12-OA2)") (class "Default")
      (node (ref "IC12") (pin "32") (pinfunction "OA2_32") (pintype "bidirectional"))
      (node (ref "X17") (pin "1") (pinfunction "S_1") (pintype "passive"))
    )
    (net (code "149") (name "Net-(IC12-OB1)") (class "Default")
      (node (ref "IC12") (pin "13") (pinfunction "OB1_13") (pintype "bidirectional"))
      (node (ref "X17") (pin "3") (pinfunction "S_3") (pintype "passive"))
    )
    (net (code "150") (name "Net-(IC12-OB2)") (class "Default")
      (node (ref "IC12") (pin "15") (pinfunction "OB2_15") (pintype "bidirectional"))
      (node (ref "X17") (pin "4") (pinfunction "S_4") (pintype "passive"))
    )
    (net (code "151") (name "Net-(IC12-SCK_CFG2)") (class "Default")
      (node (ref "IC12") (pin "3") (pinfunction "SCK_CFG2_3") (pintype "bidirectional"))
      (node (ref "IC13") (pin "4") (pinfunction "O_4") (pintype "output"))
    )
    (net (code "152") (name "Net-(IC12-SDI_NAI_CFG1)") (class "Default")
      (node (ref "IC12") (pin "4") (pinfunction "SDI_NAI_CFG1_4") (pintype "bidirectional"))
      (node (ref "IC14") (pin "4") (pinfunction "O_4") (pintype "output"))
    )
    (net (code "153") (name "Net-(IC12-SDO_NAO_CFG0)") (class "Default")
      (node (ref "IC12") (pin "5") (pinfunction "SDO_NAO_CFG0_5") (pintype "bidirectional"))
      (node (ref "U4") (pin "3") (pinfunction "QD_3") (pintype "output"))
    )
    (net (code "154") (name "Net-(IC12-VCC)") (class "Default")
      (node (ref "C74") (pin "1") (pinfunction "1_1") (pintype "passive"))
      (node (ref "IC12") (pin "26") (pinfunction "VCC_26") (pintype "bidirectional"))
      (node (ref "R71") (pin "2") (pinfunction "2_2") (pintype "passive"))
    )
    (net (code "155") (name "Net-(IC12-VCP)") (class "Default")
      (node (ref "C66") (pin "1") (pinfunction "1_1") (pintype "passive"))
      (node (ref "IC12") (pin "29") (pinfunction "VCP_29") (pintype "bidirectional"))
    )
    (net (code "156") (name "Net-(IC13A-I)") (class "Default")
      (node (ref "IC13") (pin "2") (pinfunction "I_2") (pintype "input"))
      (node (ref "U4") (pin "4") (pinfunction "QE_4") (pintype "output"))
    )
    (net (code "157") (name "Net-(IC13A-OE)") (class "Default")
      (node (ref "IC13") (pin "1") (pinfunction "OE_1") (pintype "input"))
      (node (ref "U4") (pin "5") (pinfunction "QF_5") (pintype "output"))
    )
    (net (code "158") (name "Net-(IC14A-I)") (class "Default")
      (node (ref "IC14") (pin "2") (pinfunction "I_2") (pintype "input"))
      (node (ref "U4") (pin "6") (pinfunction "QG_6") (pintype "output"))
    )
    (net (code "159") (name "Net-(IC14A-OE)") (class "Default")
      (node (ref "IC14") (pin "1") (pinfunction "OE_1") (pintype "input"))
      (node (ref "U4") (pin "7") (pinfunction "QH_7") (pintype "output"))
    )
    (net (code "160") (name "Net-(IC15-5VOUT)") (class "Default")
      (node (ref "C68") (pin "2") (pinfunction "2_2") (pintype "passive"))
      (node (ref "IC15") (pin "25") (pinfunction "5VOUT_25") (pintype "bidirectional"))
      (node (ref "R52") (pin "1") (pinfunction "1_1") (pintype "passive"))
    )
    (net (code "161") (name "Net-(IC15-AIN_IREF)") (class "Default")
      (node (ref "C36") (pin "1") (pinfunction "1_1") (pintype "passive"))
      (node (ref "IC15") (pin "23") (pinfunction "AIN_IREF_23") (pintype "bidirectional"))
      (node (ref "R50") (pin "1") (pinfunction "1_1") (pintype "passive"))
    )
    (net (code "162") (name "Net-(IC15-BRA)") (class "Default")
      (node (ref "IC15") (pin "33") (pinfunction "BRA_33") (pintype "bidirectional"))
      (node (ref "R10") (pin "2") (pinfunction "2_2") (pintype "passive"))
    )
    (net (code "163") (name "Net-(IC15-BRB)") (class "Default")
      (node (ref "IC15") (pin "14") (pinfunction "BRB_14") (pintype "bidirectional"))
      (node (ref "R9") (pin "2") (pinfunction "2_2") (pintype "passive"))
    )
    (net (code "164") (name "Net-(IC15-CPI)") (class "Default")
      (node (ref "C9") (pin "1") (pinfunction "1_1") (pintype "passive"))
      (node (ref "IC15") (pin "28") (pinfunction "CPI_28") (pintype "bidirectional"))
    )
    (net (code "165") (name "Net-(IC15-CPO)") (class "Default")
      (node (ref "C9") (pin "2") (pinfunction "2_2") (pintype "passive"))
      (node (ref "IC15") (pin "27") (pinfunction "CPO_27") (pintype "bidirectional"))
    )
    (net (code "166") (name "Net-(IC15-ENCA_DCIN_CFG5)") (class "Default")
      (node (ref "IC15") (pin "19") (pinfunction "ENCA_DCIN_CFG5_19") (pintype "bidirectional"))
      (node (ref "U5") (pin "1") (pinfunction "QB_1") (pintype "output"))
    )
    (net (code "167") (name "Net-(IC15-ENCB_DCEN_CFG4)") (class "Default")
      (node (ref "IC15") (pin "18") (pinfunction "ENCB_DCEN_CFG4_18") (pintype "bidirectional"))
      (node (ref "U5") (pin "2") (pinfunction "QC_2") (pintype "output"))
    )
    (net (code "168") (name "Net-(IC15-OA1)") (class "Default")
      (node (ref "IC15") (pin "34") (pinfunction "OA1_34") (pintype "bidirectional"))
      (node (ref "X18") (pin "2") (pinfunction "S_2") (pintype "passive"))
    )
    (net (code "169") (name "Net-(IC15-OA2)") (class "Default")
      (node (ref "IC15") (pin "32") (pinfunction "OA2_32") (pintype "bidirectional"))
      (node (ref "X18") (pin "1") (pinfunction "S_1") (pintype "passive"))
    )
    (net (code "170") (name "Net-(IC15-OB1)") (class "Default")
      (node (ref "IC15") (pin "13") (pinfunction "OB1_13") (pintype "bidirectional"))
      (node (ref "X18") (pin "3") (pinfunction "S_3") (pintype "passive"))
    )
    (net (code "171") (name "Net-(IC15-OB2)") (class "Default")
      (node (ref "IC15") (pin "15") (pinfunction "OB2_15") (pintype "bidirectional"))
      (node (ref "X18") (pin "4") (pinfunction "S_4") (pintype "passive"))
    )
    (net (code "172") (name "Net-(IC15-SCK_CFG2)") (class "Default")
      (node (ref "IC15") (pin "3") (pinfunction "SCK_CFG2_3") (pintype "bidirectional"))
      (node (ref "IC16") (pin "4") (pinfunction "O_4") (pintype "output"))
    )
    (net (code "173") (name "Net-(IC15-SDI_NAI_CFG1)") (class "Default")
      (node (ref "IC15") (pin "4") (pinfunction "SDI_NAI_CFG1_4") (pintype "bidirectional"))
      (node (ref "IC17") (pin "4") (pinfunction "O_4") (pintype "output"))
    )
    (net (code "174") (name "Net-(IC15-SDO_NAO_CFG0)") (class "Default")
      (node (ref "IC15") (pin "5") (pinfunction "SDO_NAO_CFG0_5") (pintype "bidirectional"))
      (node (ref "U5") (pin "3") (pinfunction "QD_3") (pintype "output"))
    )
    (net (code "175") (name "Net-(IC15-VCC)") (class "Default")
      (node (ref "C70") (pin "1") (pinfunction "1_1") (pintype "passive"))
      (node (ref "IC15") (pin "26") (pinfunction "VCC_26") (pintype "bidirectional"))
      (node (ref "R52") (pin "2") (pinfunction "2_2") (pintype "passive"))
    )
    (net (code "176") (name "Net-(IC15-VCP)") (class "Default")
      (node (ref "C69") (pin "1") (pinfunction "1_1") (pintype "passive"))
      (node (ref "IC15") (pin "29") (pinfunction "VCP_29") (pintype "bidirectional"))
    )
    (net (code "177") (name "Net-(IC16A-I)") (class "Default")
      (node (ref "IC16") (pin "2") (pinfunction "I_2") (pintype "input"))
      (node (ref "U5") (pin "4") (pinfunction "QE_4") (pintype "output"))
    )
    (net (code "178") (name "Net-(IC16A-OE)") (class "Default")
      (node (ref "IC16") (pin "1") (pinfunction "OE_1") (pintype "input"))
      (node (ref "U5") (pin "5") (pinfunction "QF_5") (pintype "output"))
    )
    (net (code "179") (name "Net-(IC17A-I)") (class "Default")
      (node (ref "IC17") (pin "2") (pinfunction "I_2") (pintype "input"))
      (node (ref "U5") (pin "6") (pinfunction "QG_6") (pintype "output"))
    )
    (net (code "180") (name "Net-(IC17A-OE)") (class "Default")
      (node (ref "IC17") (pin "1") (pinfunction "OE_1") (pintype "input"))
      (node (ref "U5") (pin "7") (pinfunction "QH_7") (pintype "output"))
    )
    (net (code "181") (name "Net-(IC18A-I)") (class "Default")
      (node (ref "IC18") (pin "2") (pinfunction "I_2") (pintype "input"))
      (node (ref "U1") (pin "15") (pinfunction "QA_15") (pintype "output"))
    )
    (net (code "182") (name "Net-(IC19A-I)") (class "Default")
      (node (ref "IC19") (pin "2") (pinfunction "I_2") (pintype "input"))
      (node (ref "U4") (pin "15") (pinfunction "QA_15") (pintype "output"))
    )
    (net (code "183") (name "Net-(LED1-PadA)") (class "Default")
      (node (ref "LED1") (pin "A") (pinfunction "A_A") (pintype "passive"))
      (node (ref "R14") (pin "1") (pinfunction "1_1") (pintype "passive"))
    )
    (net (code "184") (name "Net-(LED2-PadA)") (class "Default")
      (node (ref "LED2") (pin "A") (pinfunction "A_A") (pintype "passive"))
      (node (ref "R16") (pin "1") (pinfunction "1_1") (pintype "passive"))
    )
    (net (code "185") (name "Net-(LED3-PadA)") (class "Default")
      (node (ref "LED3") (pin "A") (pinfunction "A_A") (pintype "passive"))
      (node (ref "R15") (pin "1") (pinfunction "1_1") (pintype "passive"))
    )
    (net (code "186") (name "Net-(LED4-PadA)") (class "Default")
      (node (ref "LED4") (pin "A") (pinfunction "A_A") (pintype "passive"))
      (node (ref "R11") (pin "1") (pinfunction "1_1") (pintype "passive"))
    )
    (net (code "187") (name "Net-(LED5-PadA)") (class "Default")
      (node (ref "LED5") (pin "A") (pinfunction "A_A") (pintype "passive"))
      (node (ref "R19") (pin "1") (pinfunction "1_1") (pintype "passive"))
    )
    (net (code "188") (name "Net-(LED6-PadA)") (class "Default")
      (node (ref "LED6") (pin "A") (pinfunction "A_A") (pintype "passive"))
      (node (ref "R20") (pin "1") (pinfunction "1_1") (pintype "passive"))
    )
    (net (code "189") (name "Net-(LED7-PadA)") (class "Default")
      (node (ref "LED7") (pin "A") (pinfunction "A_A") (pintype "passive"))
      (node (ref "R21") (pin "1") (pinfunction "1_1") (pintype "passive"))
    )
    (net (code "190") (name "Net-(LED8-PadC)") (class "Default")
      (node (ref "LED8") (pin "C") (pinfunction "C_C") (pintype "passive"))
      (node (ref "R45") (pin "2") (pinfunction "2_2") (pintype "passive"))
    )
    (net (code "191") (name "Net-(Q4-C)") (class "Default")
      (node (ref "LED6") (pin "C") (pinfunction "C_C") (pintype "passive"))
      (node (ref "Q4") (pin "3") (pinfunction "C_3") (pintype "passive"))
      (node (ref "X5") (pin "2") (pinfunction "S_2") (pintype "passive"))
    )
    (net (code "192") (name "Net-(Q5-C)") (class "Default")
      (node (ref "LED7") (pin "C") (pinfunction "C_C") (pintype "passive"))
      (node (ref "Q5") (pin "3") (pinfunction "C_3") (pintype "passive"))
      (node (ref "X6") (pin "2") (pinfunction "S_2") (pintype "passive"))
    )
    (net (code "193") (name "Net-(Q6-C)") (class "Default")
      (node (ref "FAN0") (pin "C") (pinfunction "C_C") (pintype "passive"))
      (node (ref "Q6") (pin "3") (pinfunction "C_3") (pintype "passive"))
      (node (ref "X9") (pin "2") (pinfunction "S_2") (pintype "passive"))
    )
    (net (code "194") (name "Net-(Q7-C)") (class "Default")
      (node (ref "LED5") (pin "C") (pinfunction "C_C") (pintype "passive"))
      (node (ref "Q7") (pin "3") (pinfunction "C_3") (pintype "passive"))
      (node (ref "X4") (pin "2") (pinfunction "S_2") (pintype "passive"))
    )
    (net (code "195") (name "Net-(U6-BOOT)") (class "Default")
      (node (ref "C50") (pin "1") (pinfunction "1_1") (pintype "passive"))
      (node (ref "U6") (pin "2") (pinfunction "BOOT_2") (pintype "input"))
    )
    (net (code "196") (name "Net-(U6-COMP)") (class "Default")
      (node (ref "C51") (pin "1") (pinfunction "1_1") (pintype "passive"))
      (node (ref "U6") (pin "8") (pinfunction "COMP_8") (pintype "bidirectional"))
    )
    (net (code "197") (name "Net-(U6-FB)") (class "Default")
      (node (ref "R12") (pin "2") (pinfunction "2_2") (pintype "passive"))
      (node (ref "R22") (pin "1") (pinfunction "1_1") (pintype "passive"))
      (node (ref "U6") (pin "7") (pinfunction "FB_7") (pintype "input"))
    )
    (net (code "198") (name "Net-(U6-SS)") (class "Default")
      (node (ref "C49") (pin "1") (pinfunction "1_1") (pintype "passive"))
      (node (ref "U6") (pin "10") (pinfunction "SS_10") (pintype "bidirectional"))
    )
    (net (code "199") (name "Net-(U6-SW)") (class "Default")
      (node (ref "C50") (pin "2") (pinfunction "2_2") (pintype "passive"))
      (node (ref "D6") (pin "C") (pinfunction "C_C") (pintype "passive"))
      (node (ref "L1") (pin "P$2") (pinfunction "P$2_P$2") (pintype "passive"))
      (node (ref "U6") (pin "5") (pinfunction "SW_5") (pintype "power_in"))
    )
    (net (code "200") (name "Net-(U10-BOOT)") (class "Default")
      (node (ref "C55") (pin "1") (pinfunction "1_1") (pintype "passive"))
      (node (ref "U10") (pin "2") (pinfunction "BOOT_2") (pintype "input"))
    )
    (net (code "201") (name "Net-(U10-COMP)") (class "Default")
      (node (ref "C56") (pin "1") (pinfunction "1_1") (pintype "passive"))
      (node (ref "U10") (pin "8") (pinfunction "COMP_8") (pintype "bidirectional"))
    )
    (net (code "202") (name "Net-(U10-FB)") (class "Default")
      (node (ref "R42") (pin "2") (pinfunction "2_2") (pintype "passive"))
      (node (ref "R43") (pin "1") (pinfunction "1_1") (pintype "passive"))
      (node (ref "U10") (pin "7") (pinfunction "FB_7") (pintype "input"))
    )
    (net (code "203") (name "Net-(U10-SS)") (class "Default")
      (node (ref "C54") (pin "1") (pinfunction "1_1") (pintype "passive"))
      (node (ref "U10") (pin "10") (pinfunction "SS_10") (pintype "bidirectional"))
    )
    (net (code "204") (name "Net-(U10-SW)") (class "Default")
      (node (ref "C55") (pin "2") (pinfunction "2_2") (pintype "passive"))
      (node (ref "D4") (pin "C") (pinfunction "C_C") (pintype "passive"))
      (node (ref "L2") (pin "P$2") (pinfunction "P$2_P$2") (pintype "passive"))
      (node (ref "U10") (pin "5") (pinfunction "SW_5") (pintype "power_in"))
    )
    (net (code "205") (name "Net-(X3B-1)") (class "Default")
      (node (ref "C59") (pin "1") (pinfunction "1_1") (pintype "passive"))
      (node (ref "D1") (pin "A") (pinfunction "A_A") (pintype "passive"))
      (node (ref "LED3") (pin "C") (pinfunction "C_C") (pintype "passive"))
      (node (ref "Q3") (pin "5") (pinfunction "D_5") (pintype "passive"))
      (node (ref "Q3") (pin "6") (pinfunction "D_6") (pintype "passive"))
      (node (ref "Q3") (pin "7") (pinfunction "D_7") (pintype "passive"))
      (node (ref "Q3") (pin "8") (pinfunction "D_8") (pintype "passive"))
      (node (ref "Q3") (pin "TH") (pinfunction "D_TH") (pintype "passive"))
      (node (ref "R55") (pin "1") (pinfunction "1_1") (pintype "passive"))
      (node (ref "X3") (pin "2") (pinfunction "1_2") (pintype "passive"))
    )
    (net (code "206") (name "Net-(X7B-S)") (class "Default")
      (node (ref "R17") (pin "1") (pinfunction "1_1") (pintype "passive"))
      (node (ref "R39") (pin "1") (pinfunction "1_1") (pintype "passive"))
      (node (ref "X7") (pin "2") (pinfunction "S_2") (pintype "passive"))
    )
    (net (code "207") (name "Net-(X8B-S)") (class "Default")
      (node (ref "R13") (pin "1") (pinfunction "1_1") (pintype "passive"))
      (node (ref "R38") (pin "1") (pinfunction "1_1") (pintype "passive"))
      (node (ref "X8") (pin "2") (pinfunction "S_2") (pintype "passive"))
    )
    (net (code "208") (name "Net-(X11B-S)") (class "Default")
      (node (ref "R18") (pin "1") (pinfunction "1_1") (pintype "passive"))
      (node (ref "R40") (pin "1") (pinfunction "1_1") (pintype "passive"))
      (node (ref "X11") (pin "2") (pinfunction "S_2") (pintype "passive"))
    )
    (net (code "209") (name "Net-(X20C-1)") (class "Default")
      (node (ref "C58") (pin "1") (pinfunction "1_1") (pintype "passive"))
      (node (ref "D2") (pin "A") (pinfunction "A_A") (pintype "passive"))
      (node (ref "LED2") (pin "C") (pinfunction "C_C") (pintype "passive"))
      (node (ref "Q1") (pin "5") (pinfunction "D_5") (pintype "passive"))
      (node (ref "Q1") (pin "6") (pinfunction "D_6") (pintype "passive"))
      (node (ref "Q1") (pin "7") (pinfunction "D_7") (pintype "passive"))
      (node (ref "Q1") (pin "8") (pinfunction "D_8") (pintype "passive"))
      (node (ref "Q1") (pin "TH") (pinfunction "D_TH") (pintype "passive"))
      (node (ref "R56") (pin "1") (pinfunction "1_1") (pintype "passive"))
      (node (ref "X20") (pin "3") (pinfunction "1_3") (pintype "passive"))
      (node (ref "X20") (pin "4") (pinfunction "1_4") (pintype "passive"))
    )
    (net (code "210") (name "Net-(X21B-1)") (class "Default")
      (node (ref "C57") (pin "1") (pinfunction "1_1") (pintype "passive"))
      (node (ref "D3") (pin "A") (pinfunction "A_A") (pintype "passive"))
      (node (ref "LED1") (pin "C") (pinfunction "C_C") (pintype "passive"))
      (node (ref "Q2") (pin "5") (pinfunction "D_5") (pintype "passive"))
      (node (ref "Q2") (pin "6") (pinfunction "D_6") (pintype "passive"))
      (node (ref "Q2") (pin "7") (pinfunction "D_7") (pintype "passive"))
      (node (ref "Q2") (pin "8") (pinfunction "D_8") (pintype "passive"))
      (node (ref "Q2") (pin "TH") (pinfunction "D_TH") (pintype "passive"))
      (node (ref "R57") (pin "1") (pinfunction "1_1") (pintype "passive"))
      (node (ref "X21") (pin "2") (pinfunction "1_2") (pintype "passive"))
    )
    (net (code "211") (name "unconnected-(IC1-CSN_CFG3-Pad2)") (class "Default")
      (node (ref "IC1") (pin "2") (pinfunction "CSN_CFG3_2") (pintype "bidirectional"))
    )
    (net (code "212") (name "unconnected-(IC1-ENCN_DCO-Pad17)") (class "Default")
      (node (ref "IC1") (pin "17") (pinfunction "ENCN_DCO_17") (pintype "bidirectional"))
    )
    (net (code "213") (name "unconnected-(IC1-SD_MODE-Pad9)") (class "Default")
      (node (ref "IC1") (pin "9") (pinfunction "SD_MODE_9") (pintype "bidirectional"))
    )
    (net (code "214") (name "unconnected-(IC1-SWP_DIAG1-Pad21)") (class "Default")
      (node (ref "IC1") (pin "21") (pinfunction "SWP_DIAG1_21") (pintype "bidirectional"))
    )
    (net (code "215") (name "unconnected-(IC2-CSN_CFG3-Pad2)") (class "Default")
      (node (ref "IC2") (pin "2") (pinfunction "CSN_CFG3_2") (pintype "bidirectional"))
    )
    (net (code "216") (name "unconnected-(IC2-ENCN_DCO-Pad17)") (class "Default")
      (node (ref "IC2") (pin "17") (pinfunction "ENCN_DCO_17") (pintype "bidirectional"))
    )
    (net (code "217") (name "unconnected-(IC2-SD_MODE-Pad9)") (class "Default")
      (node (ref "IC2") (pin "9") (pinfunction "SD_MODE_9") (pintype "bidirectional"))
    )
    (net (code "218") (name "unconnected-(IC2-SWP_DIAG1-Pad21)") (class "Default")
      (node (ref "IC2") (pin "21") (pinfunction "SWP_DIAG1_21") (pintype "bidirectional"))
    )
    (net (code "219") (name "unconnected-(IC5-CSN_CFG3-Pad2)") (class "Default")
      (node (ref "IC5") (pin "2") (pinfunction "CSN_CFG3_2") (pintype "bidirectional"))
    )
    (net (code "220") (name "unconnected-(IC5-ENCN_DCO-Pad17)") (class "Default")
      (node (ref "IC5") (pin "17") (pinfunction "ENCN_DCO_17") (pintype "bidirectional"))
    )
    (net (code "221") (name "unconnected-(IC5-SD_MODE-Pad9)") (class "Default")
      (node (ref "IC5") (pin "9") (pinfunction "SD_MODE_9") (pintype "bidirectional"))
    )
    (net (code "222") (name "unconnected-(IC5-SWP_DIAG1-Pad21)") (class "Default")
      (node (ref "IC5") (pin "21") (pinfunction "SWP_DIAG1_21") (pintype "bidirectional"))
    )
    (net (code "223") (name "unconnected-(IC12-CSN_CFG3-Pad2)") (class "Default")
      (node (ref "IC12") (pin "2") (pinfunction "CSN_CFG3_2") (pintype "bidirectional"))
    )
    (net (code "224") (name "unconnected-(IC12-ENCN_DCO-Pad17)") (class "Default")
      (node (ref "IC12") (pin "17") (pinfunction "ENCN_DCO_17") (pintype "bidirectional"))
    )
    (net (code "225") (name "unconnected-(IC12-SD_MODE-Pad9)") (class "Default")
      (node (ref "IC12") (pin "9") (pinfunction "SD_MODE_9") (pintype "bidirectional"))
    )
    (net (code "226") (name "unconnected-(IC12-SWP_DIAG1-Pad21)") (class "Default")
      (node (ref "IC12") (pin "21") (pinfunction "SWP_DIAG1_21") (pintype "bidirectional"))
    )
    (net (code "227") (name "unconnected-(IC15-CSN_CFG3-Pad2)") (class "Default")
      (node (ref "IC15") (pin "2") (pinfunction "CSN_CFG3_2") (pintype "bidirectional"))
    )
    (net (code "228") (name "unconnected-(IC15-ENCN_DCO-Pad17)") (class "Default")
      (node (ref "IC15") (pin "17") (pinfunction "ENCN_DCO_17") (pintype "bidirectional"))
    )
    (net (code "229") (name "unconnected-(IC15-SD_MODE-Pad9)") (class "Default")
      (node (ref "IC15") (pin "9") (pinfunction "SD_MODE_9") (pintype "bidirectional"))
    )
    (net (code "230") (name "unconnected-(IC15-SWP_DIAG1-Pad21)") (class "Default")
      (node (ref "IC15") (pin "21") (pinfunction "SWP_DIAG1_21") (pintype "bidirectional"))
    )
    (net (code "231") (name "unconnected-(P8-Pad3)") (class "Default")
      (node (ref "P8") (pin "3") (pinfunction "3_3") (pintype "passive"))
    )
    (net (code "232") (name "unconnected-(P8-Pad4)") (class "Default")
      (node (ref "P8") (pin "4") (pinfunction "4_4") (pintype "passive"))
    )
    (net (code "233") (name "unconnected-(P8-Pad5)") (class "Default")
      (node (ref "P8") (pin "5") (pinfunction "5_5") (pintype "passive"))
    )
    (net (code "234") (name "unconnected-(P8-Pad6)") (class "Default")
      (node (ref "P8") (pin "6") (pinfunction "6_6") (pintype "passive"))
    )
    (net (code "235") (name "unconnected-(P8-Pad7)") (class "Default")
      (node (ref "P8") (pin "7") (pinfunction "7_7") (pintype "passive"))
    )
    (net (code "236") (name "unconnected-(P8-Pad20)") (class "Default")
      (node (ref "P8") (pin "20") (pinfunction "20_20") (pintype "passive"))
    )
    (net (code "237") (name "unconnected-(P8-Pad21)") (class "Default")
      (node (ref "P8") (pin "21") (pinfunction "21_21") (pintype "passive"))
    )
    (net (code "238") (name "unconnected-(P8-Pad22)") (class "Default")
      (node (ref "P8") (pin "22") (pinfunction "22_22") (pintype "passive"))
    )
    (net (code "239") (name "unconnected-(P8-Pad23)") (class "Default")
      (node (ref "P8") (pin "23") (pinfunction "23_23") (pintype "passive"))
    )
    (net (code "240") (name "unconnected-(P8-Pad24)") (class "Default")
      (node (ref "P8") (pin "24") (pinfunction "24_24") (pintype "passive"))
    )
    (net (code "241") (name "unconnected-(P8-Pad25)") (class "Default")
      (node (ref "P8") (pin "25") (pinfunction "25_25") (pintype "passive"))
    )
    (net (code "242") (name "unconnected-(P8-Pad27)") (class "Default")
      (node (ref "P8") (pin "27") (pinfunction "27_27") (pintype "passive"))
    )
    (net (code "243") (name "unconnected-(P8-Pad28)") (class "Default")
      (node (ref "P8") (pin "28") (pinfunction "28_28") (pintype "passive"))
    )
    (net (code "244") (name "unconnected-(P8-Pad29)") (class "Default")
      (node (ref "P8") (pin "29") (pinfunction "29_29") (pintype "passive"))
    )
    (net (code "245") (name "unconnected-(P8-Pad30)") (class "Default")
      (node (ref "P8") (pin "30") (pinfunction "30_30") (pintype "passive"))
    )
    (net (code "246") (name "unconnected-(P8-Pad31)") (class "Default")
      (node (ref "P8") (pin "31") (pinfunction "31_31") (pintype "passive"))
    )
    (net (code "247") (name "unconnected-(P8-Pad32)") (class "Default")
      (node (ref "P8") (pin "32") (pinfunction "32_32") (pintype "passive"))
    )
    (net (code "248") (name "unconnected-(P8-Pad33)") (class "Default")
      (node (ref "P8") (pin "33") (pinfunction "33_33") (pintype "passive"))
    )
    (net (code "249") (name "unconnected-(P8-Pad34)") (class "Default")
      (node (ref "P8") (pin "34") (pinfunction "34_34") (pintype "passive"))
    )
    (net (code "250") (name "unconnected-(P8-Pad35)") (class "Default")
      (node (ref "P8") (pin "35") (pinfunction "35_35") (pintype "passive"))
    )
    (net (code "251") (name "unconnected-(P8-Pad36)") (class "Default")
      (node (ref "P8") (pin "36") (pinfunction "36_36") (pintype "passive"))
    )
    (net (code "252") (name "unconnected-(P8-Pad37)") (class "Default")
      (node (ref "P8") (pin "37") (pinfunction "37_37") (pintype "passive"))
    )
    (net (code "253") (name "unconnected-(P8-Pad38)") (class "Default")
      (node (ref "P8") (pin "38") (pinfunction "38_38") (pintype "passive"))
    )
    (net (code "254") (name "unconnected-(P8-Pad39)") (class "Default")
      (node (ref "P8") (pin "39") (pinfunction "39_39") (pintype "passive"))
    )
    (net (code "255") (name "unconnected-(P8-Pad40)") (class "Default")
      (node (ref "P8") (pin "40") (pinfunction "40_40") (pintype "passive"))
    )
    (net (code "256") (name "unconnected-(P8-Pad41)") (class "Default")
      (node (ref "P8") (pin "41") (pinfunction "41_41") (pintype "passive"))
    )
    (net (code "257") (name "unconnected-(P8-Pad42)") (class "Default")
      (node (ref "P8") (pin "42") (pinfunction "42_42") (pintype "passive"))
    )
    (net (code "258") (name "unconnected-(P8-Pad43)") (class "Default")
      (node (ref "P8") (pin "43") (pinfunction "43_43") (pintype "passive"))
    )
    (net (code "259") (name "unconnected-(P8-Pad44)") (class "Default")
      (node (ref "P8") (pin "44") (pinfunction "44_44") (pintype "passive"))
    )
    (net (code "260") (name "unconnected-(P8-Pad45)") (class "Default")
      (node (ref "P8") (pin "45") (pinfunction "45_45") (pintype "passive"))
    )
    (net (code "261") (name "unconnected-(P8-Pad46)") (class "Default")
      (node (ref "P8") (pin "46") (pinfunction "46_46") (pintype "passive"))
    )
    (net (code "262") (name "unconnected-(P9-Pad7)") (class "Default")
      (node (ref "P9") (pin "7") (pinfunction "7_7") (pintype "passive"))
    )
    (net (code "263") (name "unconnected-(P9-Pad8)") (class "Default")
      (node (ref "P9") (pin "8") (pinfunction "8_8") (pintype "passive"))
    )
    (net (code "264") (name "unconnected-(P9-Pad9)") (class "Default")
      (node (ref "P9") (pin "9") (pinfunction "9_9") (pintype "passive"))
    )
    (net (code "265") (name "unconnected-(P9-Pad10)") (class "Default")
      (node (ref "P9") (pin "10") (pinfunction "10_10") (pintype "passive"))
    )
    (net (code "266") (name "unconnected-(P9-Pad15)") (class "Default")
      (node (ref "P9") (pin "15") (pinfunction "15_15") (pintype "passive"))
    )
    (net (code "267") (name "unconnected-(P9-Pad17)") (class "Default")
      (node (ref "P9") (pin "17") (pinfunction "17_17") (pintype "passive"))
    )
    (net (code "268") (name "unconnected-(P9-Pad21)") (class "Default")
      (node (ref "P9") (pin "21") (pinfunction "21_21") (pintype "passive"))
    )
    (net (code "269") (name "unconnected-(P9-Pad26)") (class "Default")
      (node (ref "P9") (pin "26") (pinfunction "26_26") (pintype "passive"))
    )
    (net (code "270") (name "unconnected-(P9-Pad27)") (class "Default")
      (node (ref "P9") (pin "27") (pinfunction "27_27") (pintype "passive"))
    )
    (net (code "271") (name "unconnected-(P9-Pad29)") (class "Default")
      (node (ref "P9") (pin "29") (pinfunction "29_29") (pintype "passive"))
    )
    (net (code "272") (name "unconnected-(P9-Pad34)") (class "Default")
      (node (ref "P9") (pin "34") (pinfunction "34_34") (pintype "passive"))
    )
    (net (code "273") (name "unconnected-(P9-Pad37)") (class "Default")
      (node (ref "P9") (pin "37") (pinfunction "37_37") (pintype "passive"))
    )
    (net (code "274") (name "unconnected-(P9-Pad38)") (class "Default")
      (node (ref "P9") (pin "38") (pinfunction "38_38") (pintype "passive"))
    )
    (net (code "275") (name "unconnected-(P9-Pad39)") (class "Default")
      (node (ref "P9") (pin "39") (pinfunction "39_39") (pintype "passive"))
    )
    (net (code "276") (name "unconnected-(P9-Pad40)") (class "Default")
      (node (ref "P9") (pin "40") (pinfunction "40_40") (pintype "passive"))
    )
    (net (code "277") (name "unconnected-(U5-QH_2-Pad9)") (class "Default")
      (node (ref "U5") (pin "9") (pinfunction "QH_2_9") (pintype "output"))
    )
    (net (code "278") (name "unconnected-(U6-EN-Pad9)") (class "Default")
      (node (ref "U6") (pin "9") (pinfunction "EN_9") (pintype "input"))
    )
    (net (code "279") (name "unconnected-(U10-EN-Pad9)") (class "Default")
      (node (ref "U10") (pin "9") (pinfunction "EN_9") (pintype "input"))
    )
    (net (code "280") (name "unconnected-(U11-EXTCLK-Pad25)") (class "Default")
      (node (ref "U11") (pin "25") (pinfunction "EXTCLK_25") (pintype "input"))
    )
    (net (code "281") (name "unconnected-(U11-LED0-Pad6)") (class "Default")
      (node (ref "U11") (pin "6") (pinfunction "LED0_6") (pintype "output"))
    )
    (net (code "282") (name "unconnected-(U11-LED1-Pad7)") (class "Default")
      (node (ref "U11") (pin "7") (pinfunction "LED1_7") (pintype "output"))
    )
    (net (code "283") (name "unconnected-(U11-LED2-Pad8)") (class "Default")
      (node (ref "U11") (pin "8") (pinfunction "LED2_8") (pintype "output"))
    )
    (net (code "284") (name "unconnected-(U11-LED6-Pad12)") (class "Default")
      (node (ref "U11") (pin "12") (pinfunction "LED6_12") (pintype "output"))
    )
    (net (code "285") (name "unconnected-(U18-~{WC}-Pad7)") (class "Default")
      (node (ref "U18") (pin "7") (pinfunction "~{WC}_7") (pintype "no_connect"))
    )
    (net (code "286") (name "unconnected-(U19-NC-Pad16)") (class "Default")
      (node (ref "U19") (pin "16") (pinfunction "NC_16") (pintype "no_connect"))
    )
    (net (code "287") (name "unconnected-(U19-NC_2-Pad13)") (class "Default")
      (node (ref "U19") (pin "13") (pinfunction "NC_2_13") (pintype "no_connect"))
    )
  )
)
